# stages_v70.net
KiCad netlist of a schematic drawn in EAGLE
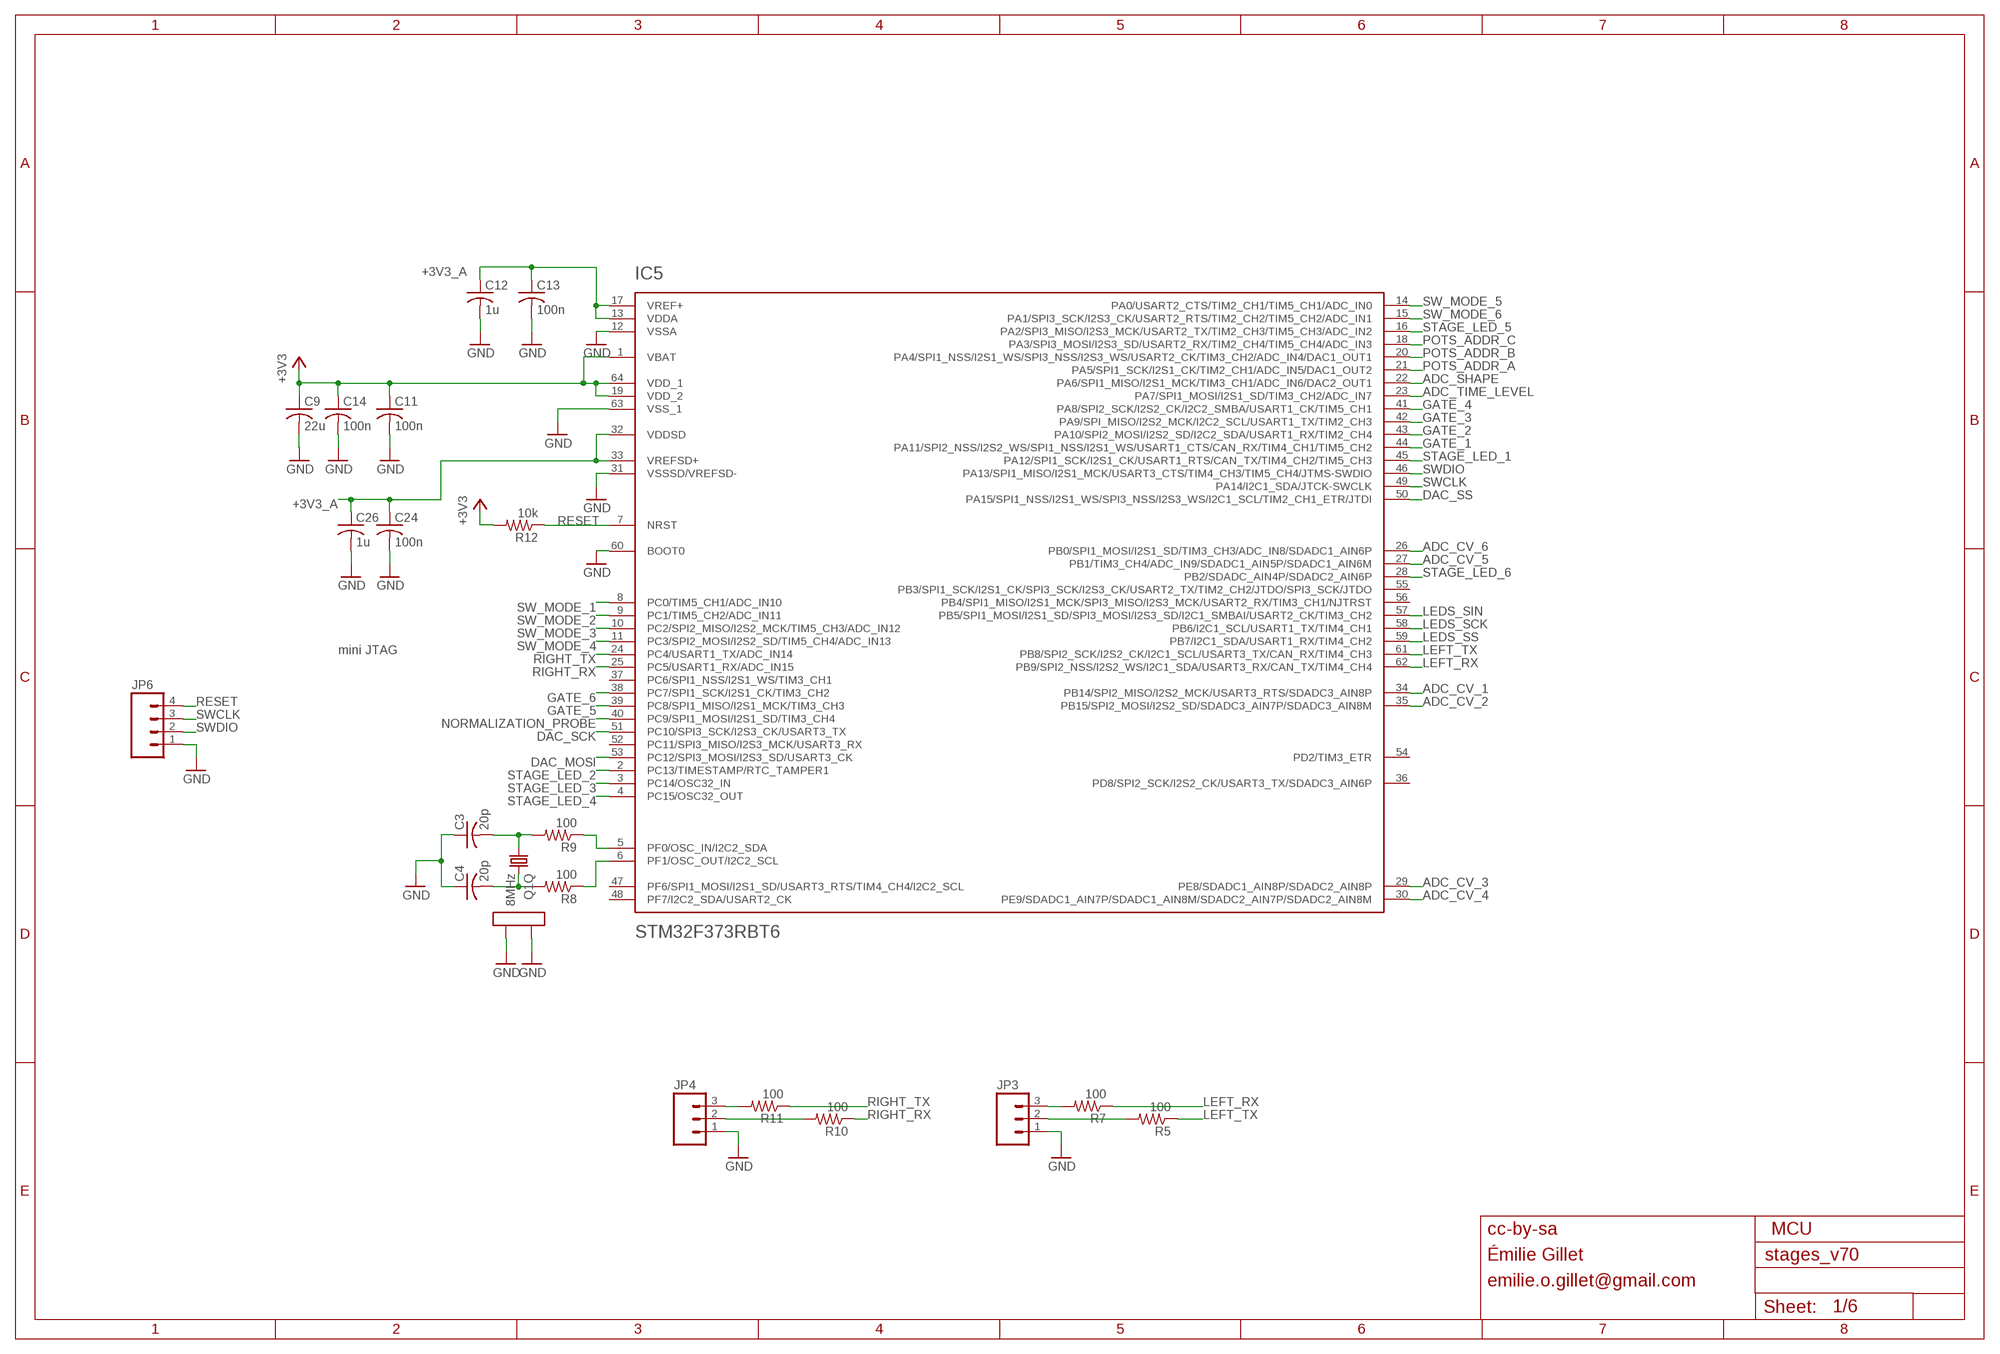
[diagram p0: schematic, sheet 1]
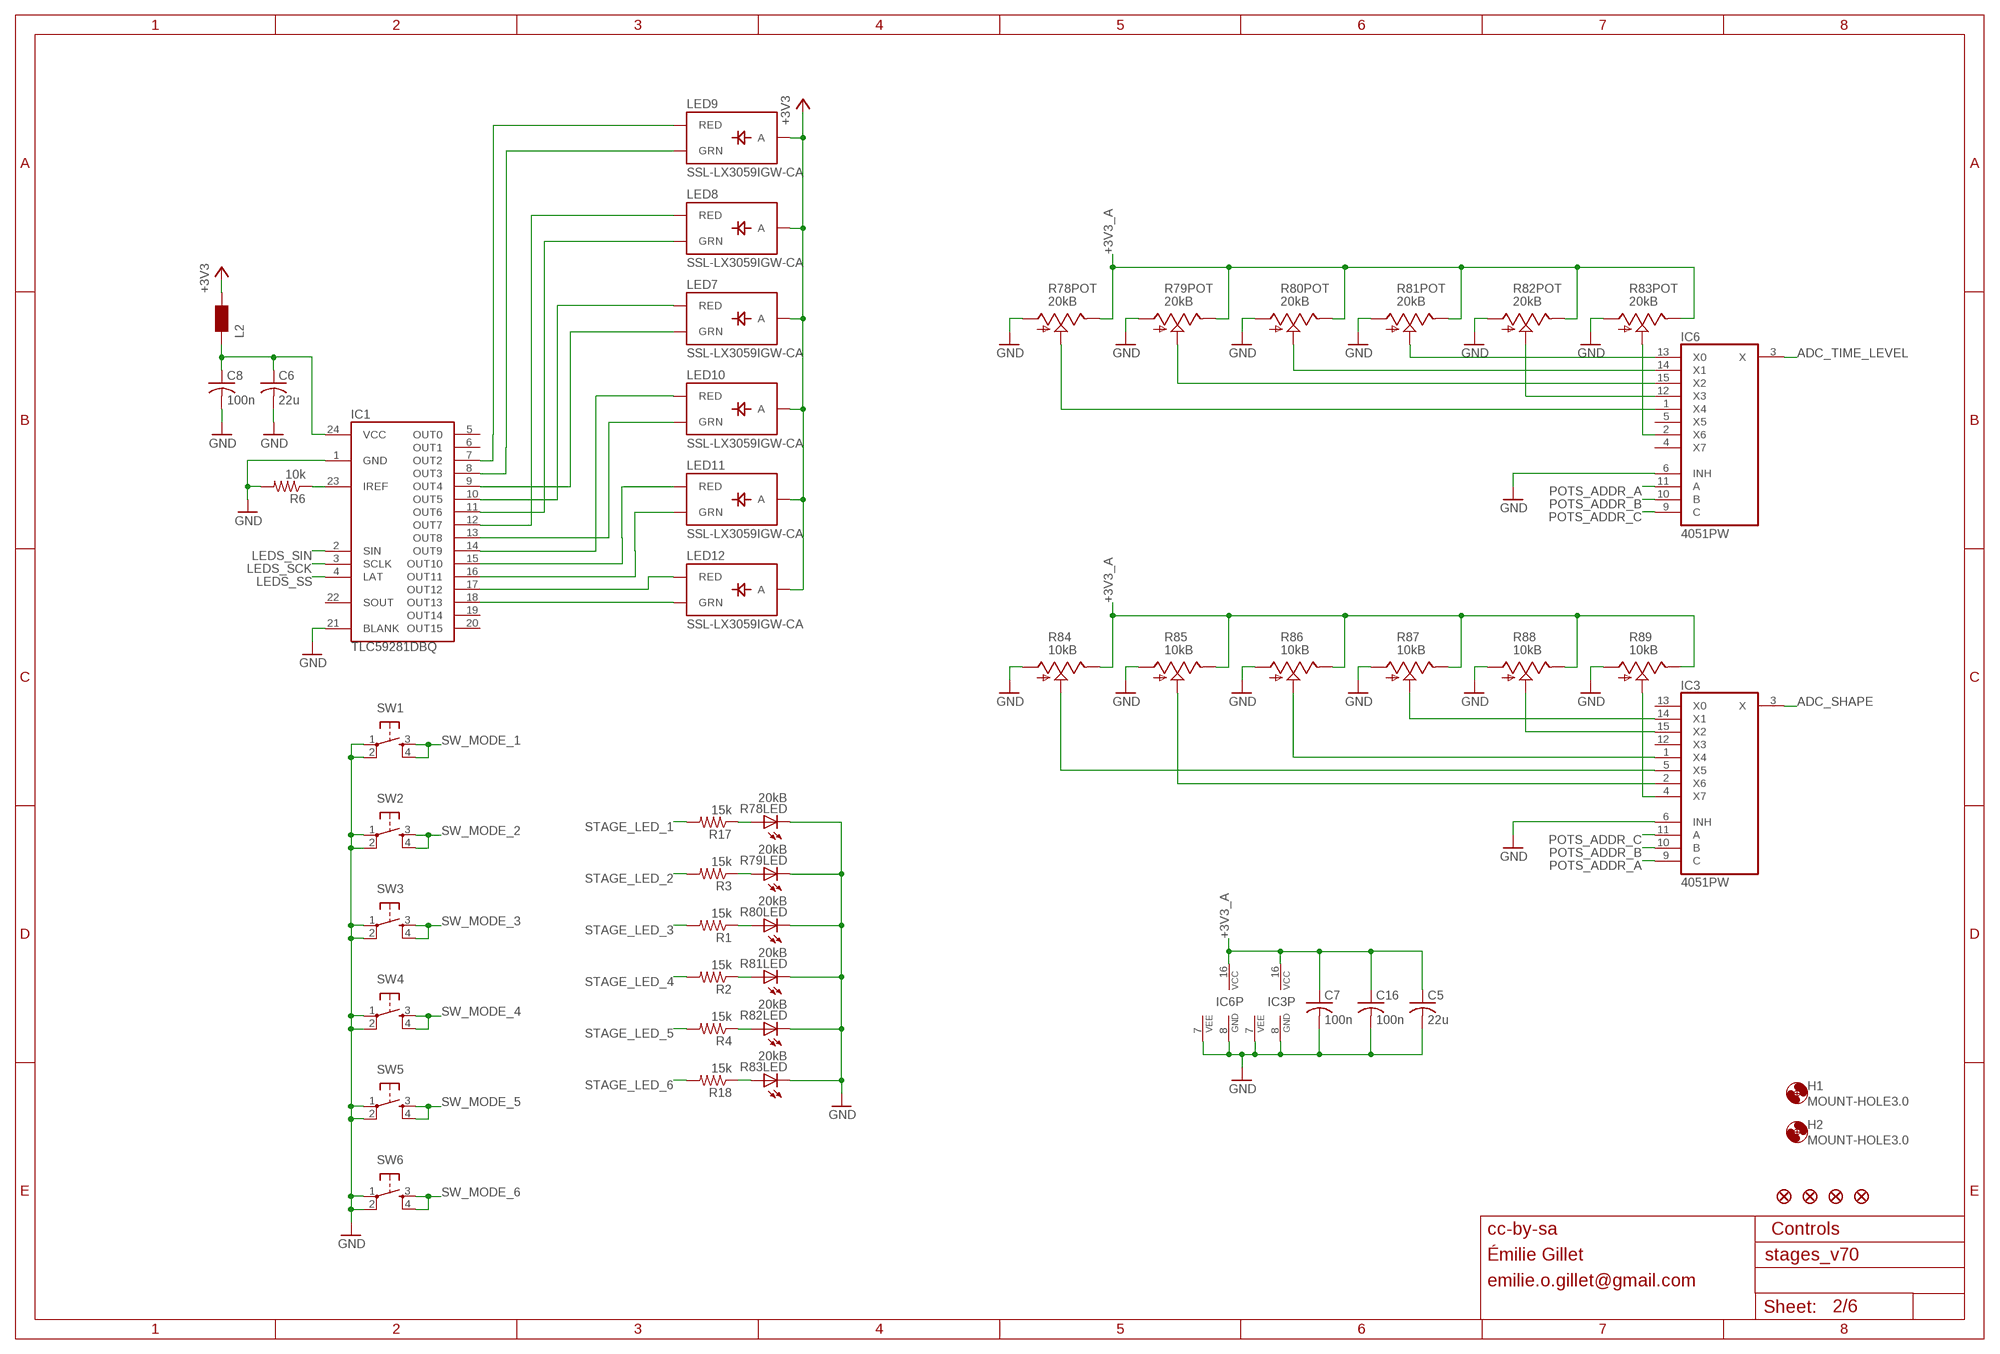
[diagram p1: schematic, sheet 2]
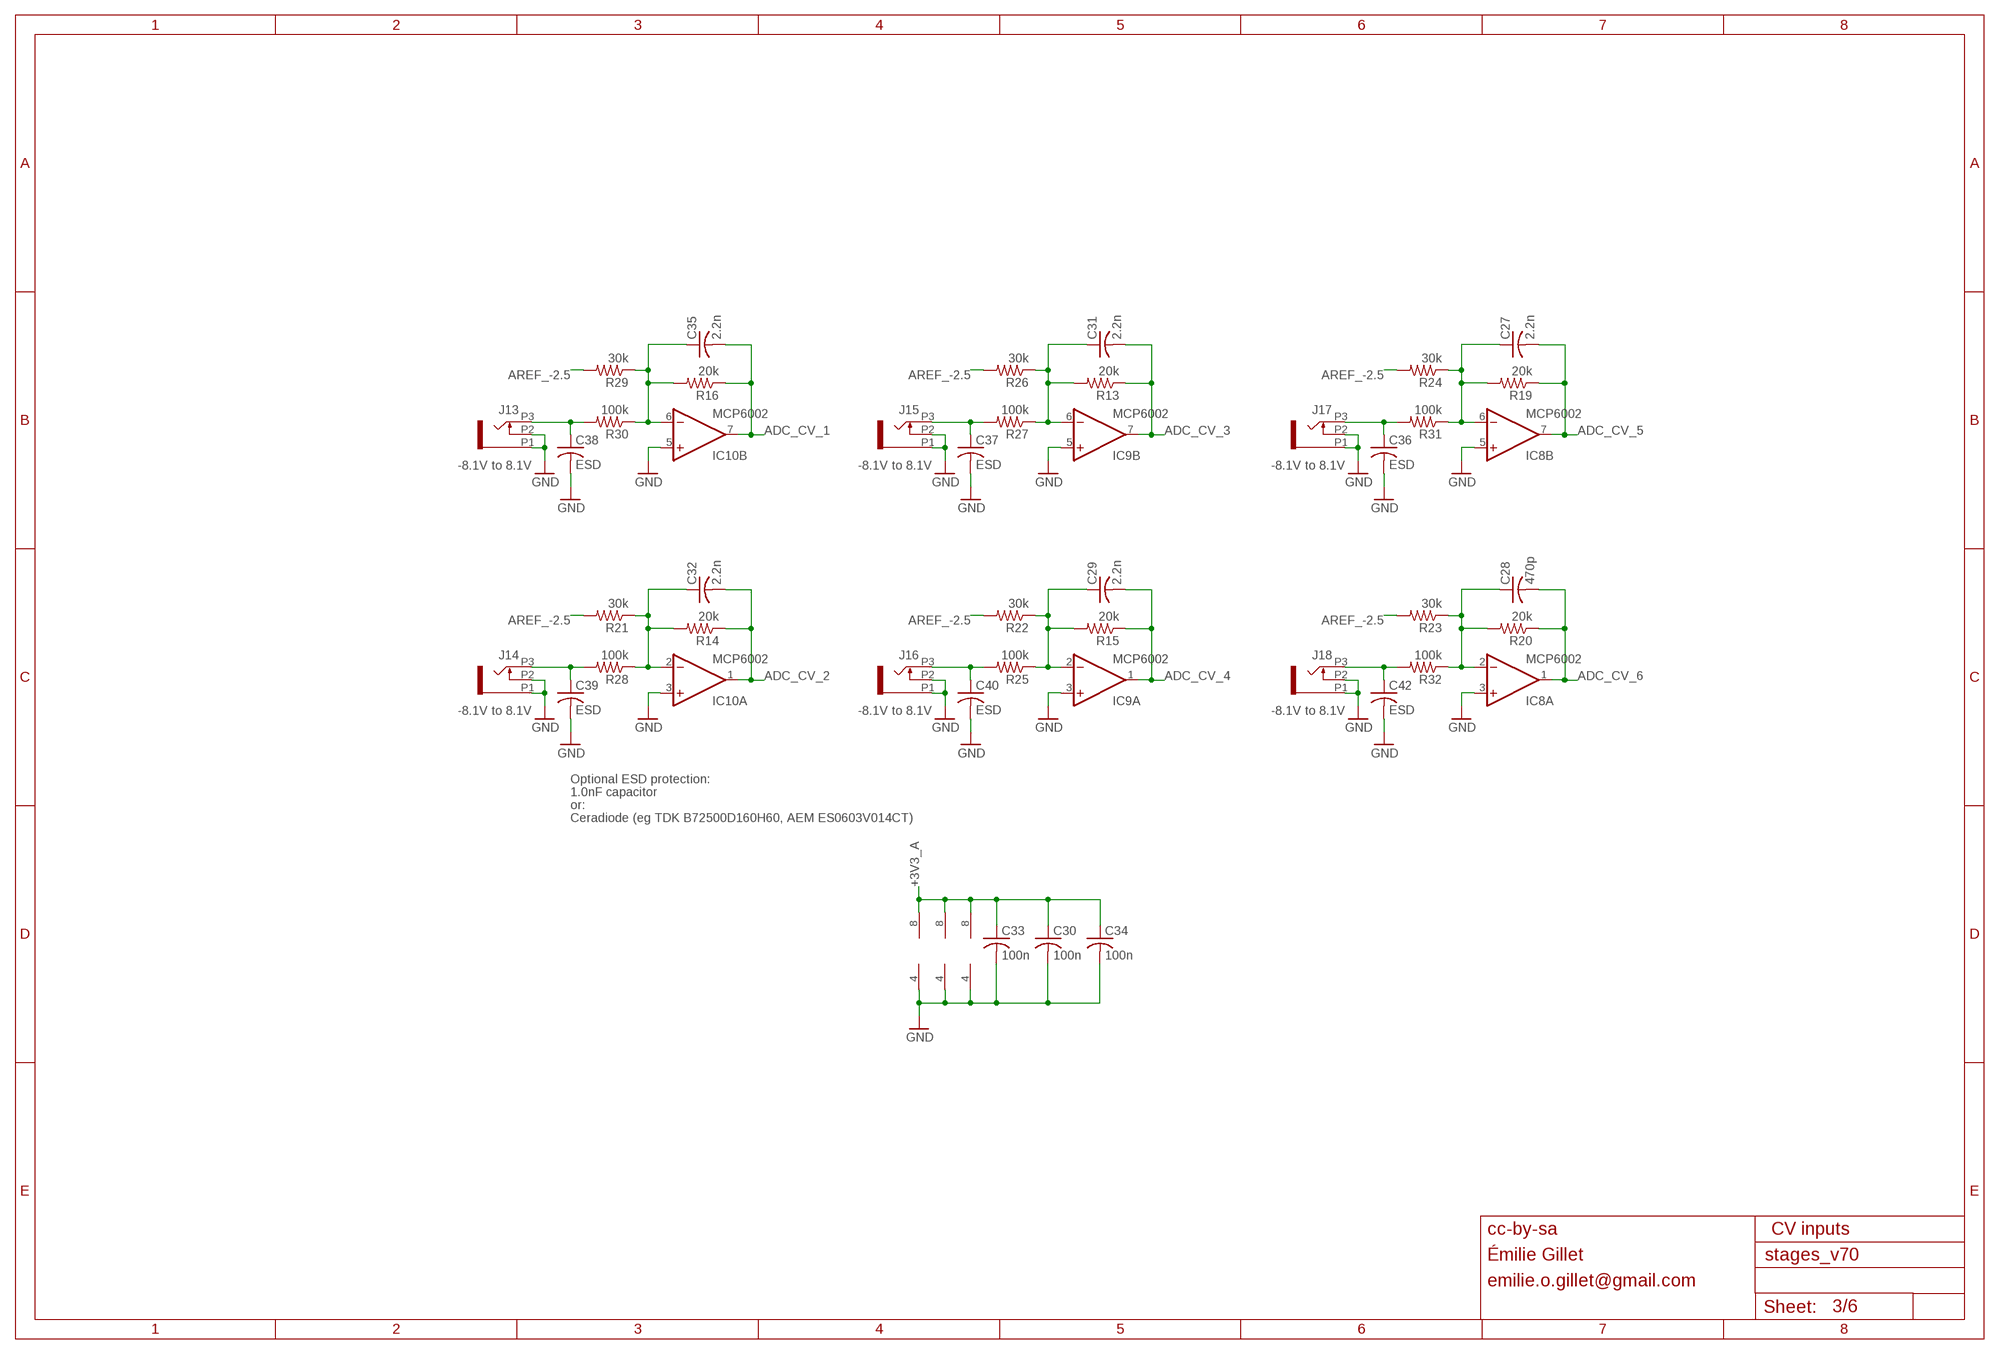
[diagram p2: schematic, sheet 3]
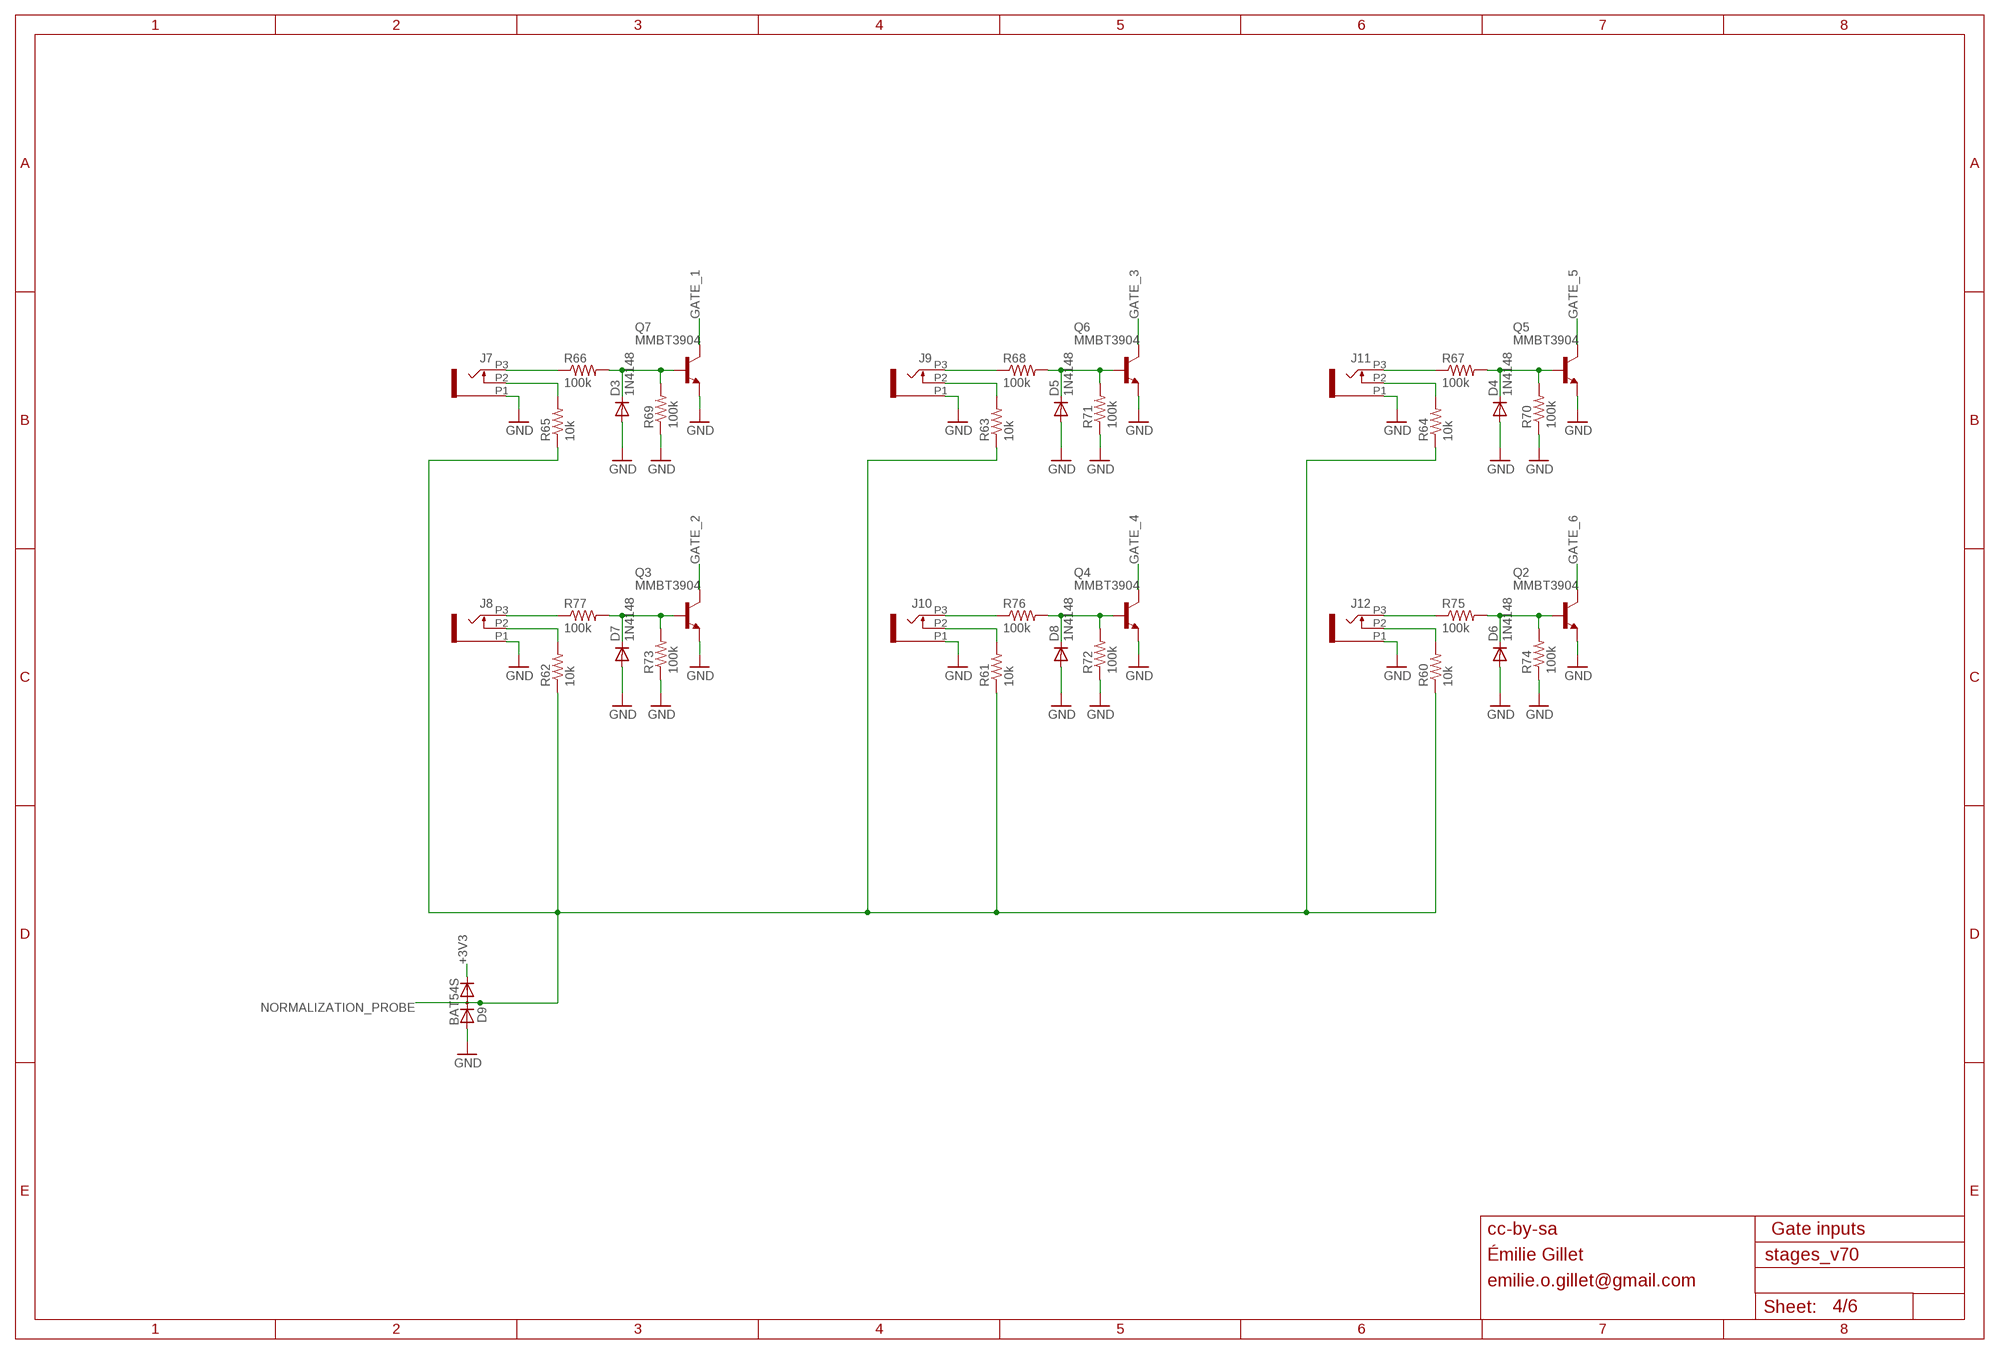
[diagram p3: schematic, sheet 4]
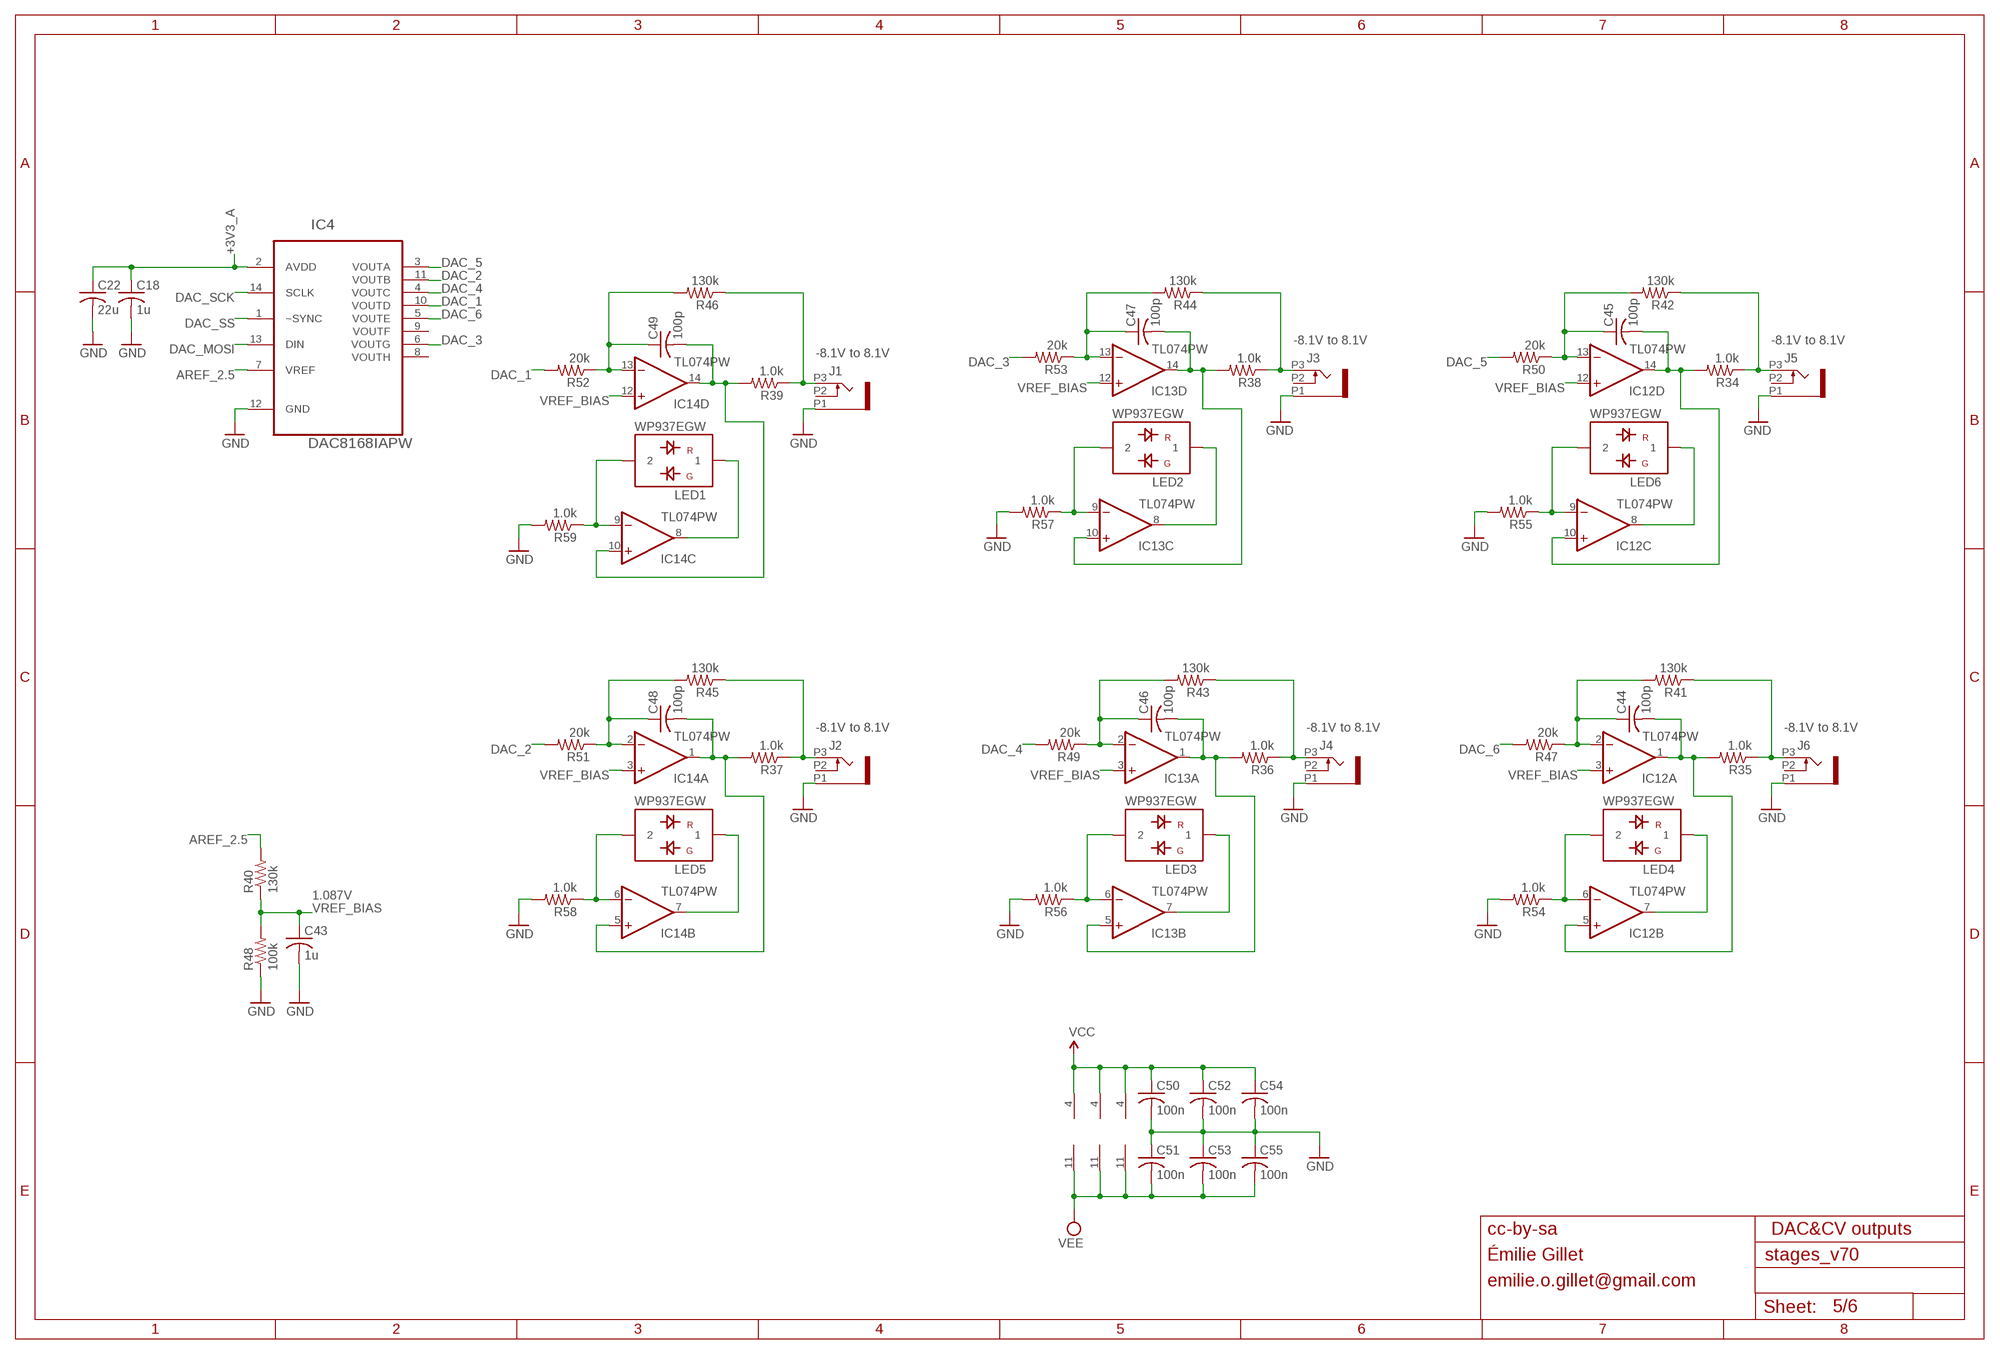
[diagram p4: schematic, sheet 5]
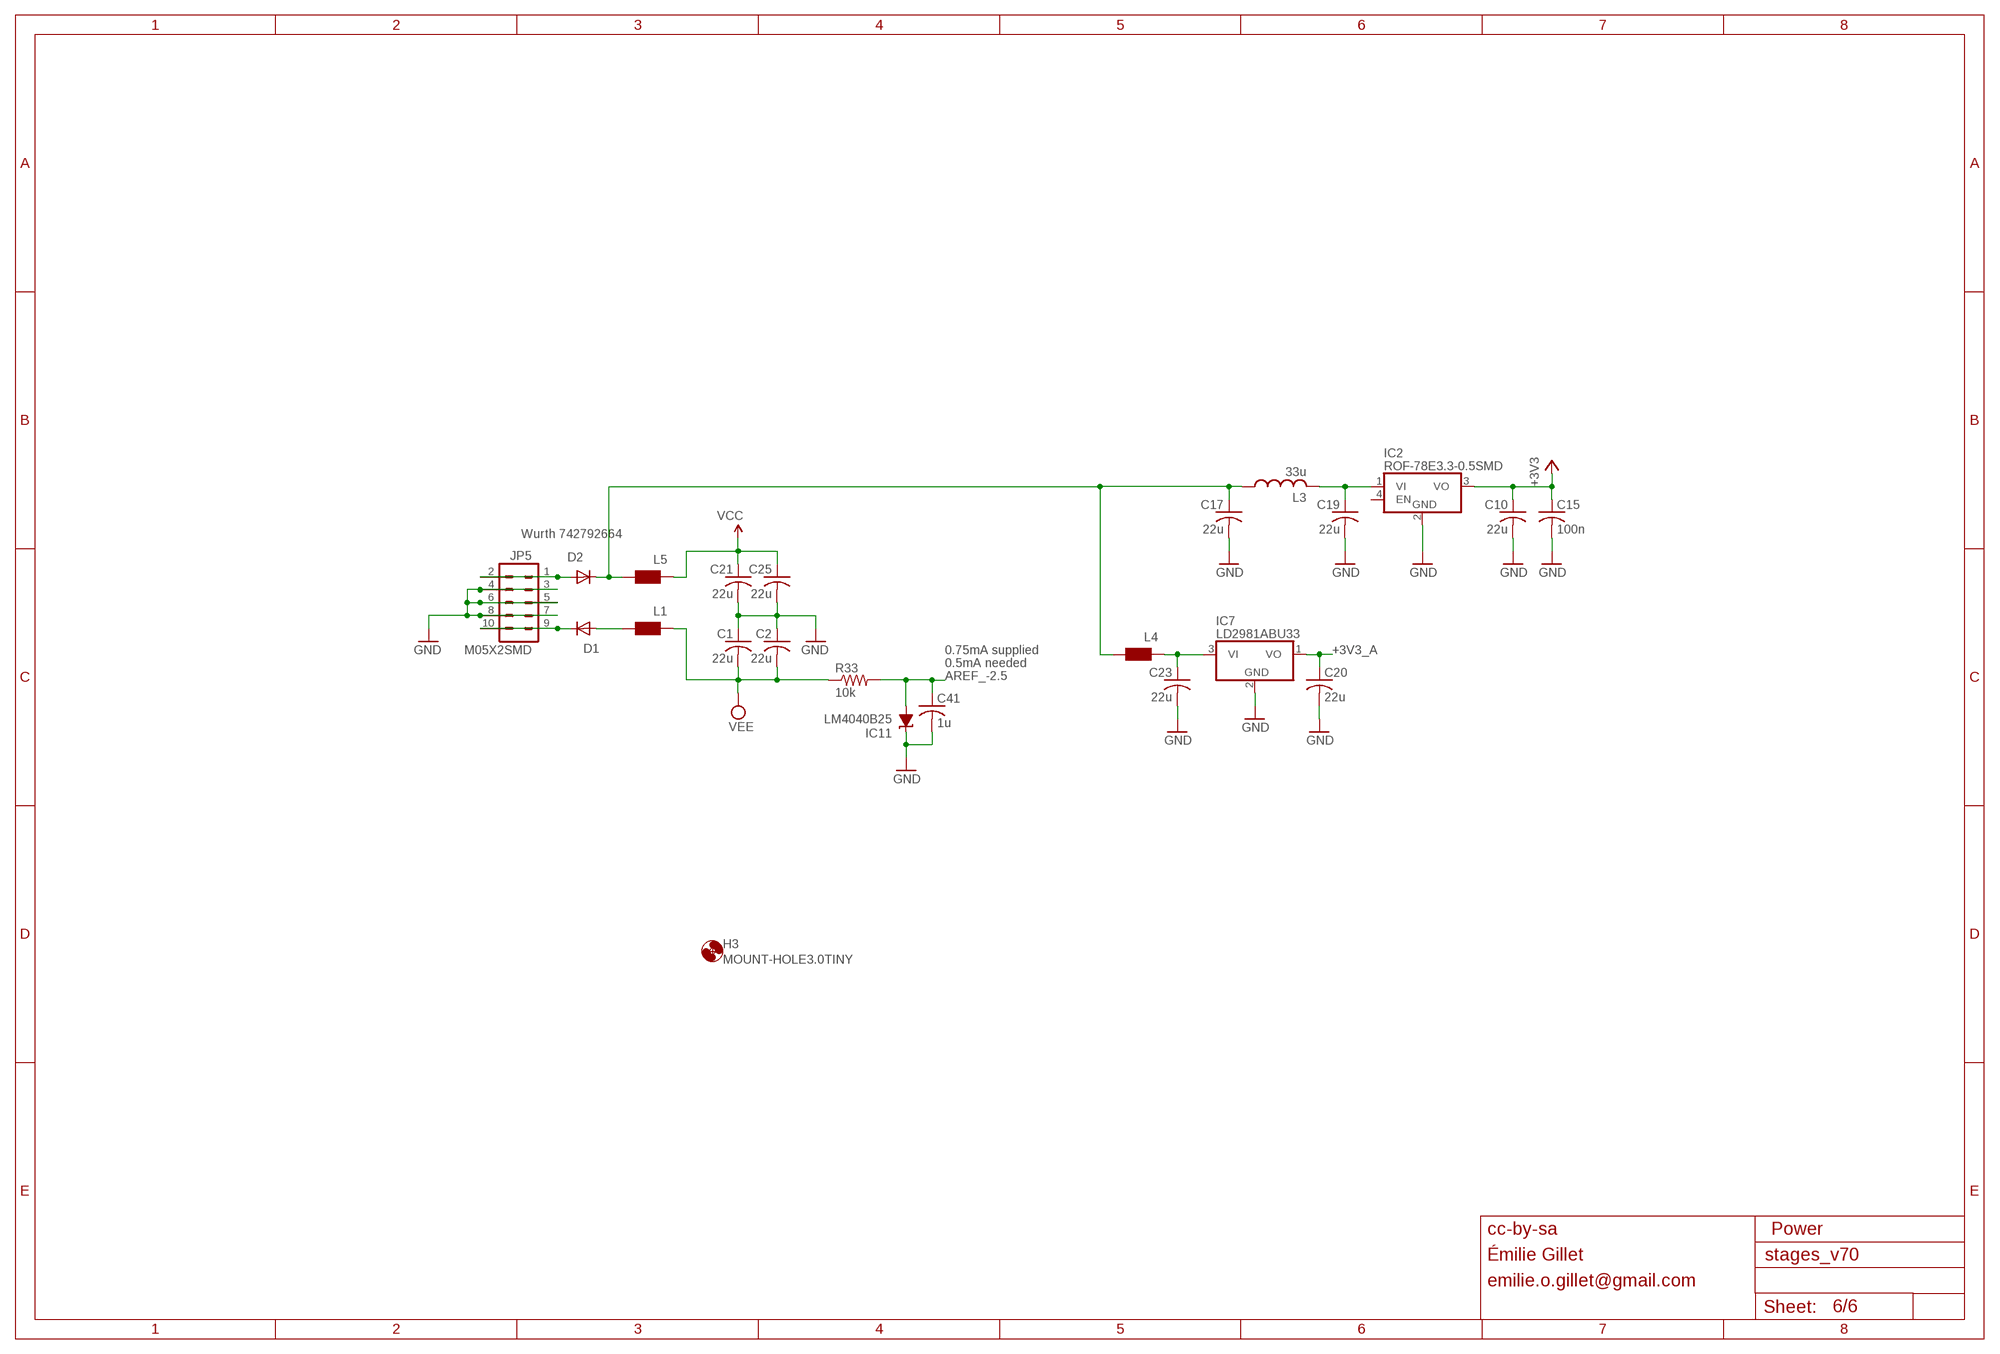
[diagram p5: schematic, sheet 6]

(export (version "E")
  (design (tool "Eeschema 10.0.6"))
  (components
    (comp (ref "C27")
      (value "2.2n")
      (footprint "eagle-import:C0402")
      (libsource (lib "eagle-import") (part "C-USC0402"))
    )
    (comp (ref "C28")
      (value "470p")
      (footprint "eagle-import:C0402")
      (libsource (lib "eagle-import") (part "C-USC0402"))
    )
    (comp (ref "C29")
      (value "2.2n")
      (footprint "eagle-import:C0402")
      (libsource (lib "eagle-import") (part "C-USC0402"))
    )
    (comp (ref "C30")
      (value "100n")
      (footprint "eagle-import:C0402")
      (libsource (lib "eagle-import") (part "C-USC0402"))
    )
    (comp (ref "C31")
      (value "2.2n")
      (footprint "eagle-import:C0402")
      (libsource (lib "eagle-import") (part "C-USC0402"))
    )
    (comp (ref "C32")
      (value "2.2n")
      (footprint "eagle-import:C0402")
      (libsource (lib "eagle-import") (part "C-USC0402"))
    )
    (comp (ref "C33")
      (value "100n")
      (footprint "eagle-import:C0402")
      (libsource (lib "eagle-import") (part "C-USC0402"))
    )
    (comp (ref "C34")
      (value "100n")
      (footprint "eagle-import:C0402")
      (libsource (lib "eagle-import") (part "C-USC0402"))
    )
    (comp (ref "C35")
      (value "2.2n")
      (footprint "eagle-import:C0402")
      (libsource (lib "eagle-import") (part "C-USC0402"))
    )
    (comp (ref "C36")
      (value "ESD")
      (footprint "eagle-import:C0603")
      (libsource (lib "eagle-import") (part "C-USC0603"))
    )
    (comp (ref "C37")
      (value "ESD")
      (footprint "eagle-import:C0603")
      (libsource (lib "eagle-import") (part "C-USC0603"))
    )
    (comp (ref "C38")
      (value "ESD")
      (footprint "eagle-import:C0603")
      (libsource (lib "eagle-import") (part "C-USC0603"))
    )
    (comp (ref "C39")
      (value "ESD")
      (footprint "eagle-import:C0603")
      (libsource (lib "eagle-import") (part "C-USC0603"))
    )
    (comp (ref "C40")
      (value "ESD")
      (footprint "eagle-import:C0603")
      (libsource (lib "eagle-import") (part "C-USC0603"))
    )
    (comp (ref "C42")
      (value "ESD")
      (footprint "eagle-import:C0603")
      (libsource (lib "eagle-import") (part "C-USC0603"))
    )
    (comp (ref "IC8")
      (value "MCP6002")
      (footprint "eagle-import:MSOP-8")
      (libsource (lib "eagle-import") (part "OPA1652DGK"))
    )
    (comp (ref "IC9")
      (value "MCP6002")
      (footprint "eagle-import:MSOP-8")
      (libsource (lib "eagle-import") (part "OPA1652DGK"))
    )
    (comp (ref "IC10")
      (value "MCP6002")
      (footprint "eagle-import:MSOP-8")
      (libsource (lib "eagle-import") (part "OPA1652DGK"))
    )
    (comp (ref "J13")
      (value "PJ301_THONKICONN6")
      (footprint "eagle-import:WQP_PJ_301M6")
      (libsource (lib "eagle-import") (part "PJ301_THONKICONN6"))
    )
    (comp (ref "J14")
      (value "PJ301_THONKICONN6")
      (footprint "eagle-import:WQP_PJ_301M6")
      (libsource (lib "eagle-import") (part "PJ301_THONKICONN6"))
    )
    (comp (ref "J15")
      (value "PJ301_THONKICONN6")
      (footprint "eagle-import:WQP_PJ_301M6")
      (libsource (lib "eagle-import") (part "PJ301_THONKICONN6"))
    )
    (comp (ref "J16")
      (value "PJ301_THONKICONN6")
      (footprint "eagle-import:WQP_PJ_301M6")
      (libsource (lib "eagle-import") (part "PJ301_THONKICONN6"))
    )
    (comp (ref "J17")
      (value "PJ301_THONKICONN6")
      (footprint "eagle-import:WQP_PJ_301M6")
      (libsource (lib "eagle-import") (part "PJ301_THONKICONN6"))
    )
    (comp (ref "J18")
      (value "PJ301_THONKICONN6")
      (footprint "eagle-import:WQP_PJ_301M6")
      (libsource (lib "eagle-import") (part "PJ301_THONKICONN6"))
    )
    (comp (ref "R13")
      (value "20k")
      (footprint "eagle-import:R0402")
      (libsource (lib "eagle-import") (part "R-US_R0402"))
    )
    (comp (ref "R14")
      (value "20k")
      (footprint "eagle-import:R0402")
      (libsource (lib "eagle-import") (part "R-US_R0402"))
    )
    (comp (ref "R15")
      (value "20k")
      (footprint "eagle-import:R0402")
      (libsource (lib "eagle-import") (part "R-US_R0402"))
    )
    (comp (ref "R16")
      (value "20k")
      (footprint "eagle-import:R0402")
      (libsource (lib "eagle-import") (part "R-US_R0402"))
    )
    (comp (ref "R19")
      (value "20k")
      (footprint "eagle-import:R0402")
      (libsource (lib "eagle-import") (part "R-US_R0402"))
    )
    (comp (ref "R20")
      (value "20k")
      (footprint "eagle-import:R0402")
      (libsource (lib "eagle-import") (part "R-US_R0402"))
    )
    (comp (ref "R21")
      (value "30k")
      (footprint "eagle-import:R0402")
      (libsource (lib "eagle-import") (part "R-US_R0402"))
    )
    (comp (ref "R22")
      (value "30k")
      (footprint "eagle-import:R0402")
      (libsource (lib "eagle-import") (part "R-US_R0402"))
    )
    (comp (ref "R23")
      (value "30k")
      (footprint "eagle-import:R0402")
      (libsource (lib "eagle-import") (part "R-US_R0402"))
    )
    (comp (ref "R24")
      (value "30k")
      (footprint "eagle-import:R0402")
      (libsource (lib "eagle-import") (part "R-US_R0402"))
    )
    (comp (ref "R25")
      (value "100k")
      (footprint "eagle-import:R0402")
      (libsource (lib "eagle-import") (part "R-US_R0402"))
    )
    (comp (ref "R26")
      (value "30k")
      (footprint "eagle-import:R0402")
      (libsource (lib "eagle-import") (part "R-US_R0402"))
    )
    (comp (ref "R27")
      (value "100k")
      (footprint "eagle-import:R0402")
      (libsource (lib "eagle-import") (part "R-US_R0402"))
    )
    (comp (ref "R28")
      (value "100k")
      (footprint "eagle-import:R0402")
      (libsource (lib "eagle-import") (part "R-US_R0402"))
    )
    (comp (ref "R29")
      (value "30k")
      (footprint "eagle-import:R0402")
      (libsource (lib "eagle-import") (part "R-US_R0402"))
    )
    (comp (ref "R30")
      (value "100k")
      (footprint "eagle-import:R0402")
      (libsource (lib "eagle-import") (part "R-US_R0402"))
    )
    (comp (ref "R31")
      (value "100k")
      (footprint "eagle-import:R0402")
      (libsource (lib "eagle-import") (part "R-US_R0402"))
    )
    (comp (ref "R32")
      (value "100k")
      (footprint "eagle-import:R0402")
      (libsource (lib "eagle-import") (part "R-US_R0402"))
    )
    (comp (ref "C18")
      (value "1u")
      (footprint "eagle-import:C0402")
      (libsource (lib "eagle-import") (part "C-USC0402"))
    )
    (comp (ref "C22")
      (value "22u")
      (footprint "eagle-import:C1206")
      (libsource (lib "eagle-import") (part "C-USC1206"))
    )
    (comp (ref "C43")
      (value "1u")
      (footprint "eagle-import:C0402")
      (libsource (lib "eagle-import") (part "C-USC0402"))
    )
    (comp (ref "C44")
      (value "100p")
      (footprint "eagle-import:C0402")
      (libsource (lib "eagle-import") (part "C-USC0402"))
    )
    (comp (ref "C45")
      (value "100p")
      (footprint "eagle-import:C0402")
      (libsource (lib "eagle-import") (part "C-USC0402"))
    )
    (comp (ref "C46")
      (value "100p")
      (footprint "eagle-import:C0402")
      (libsource (lib "eagle-import") (part "C-USC0402"))
    )
    (comp (ref "C47")
      (value "100p")
      (footprint "eagle-import:C0402")
      (libsource (lib "eagle-import") (part "C-USC0402"))
    )
    (comp (ref "C48")
      (value "100p")
      (footprint "eagle-import:C0402")
      (libsource (lib "eagle-import") (part "C-USC0402"))
    )
    (comp (ref "C49")
      (value "100p")
      (footprint "eagle-import:C0402")
      (libsource (lib "eagle-import") (part "C-USC0402"))
    )
    (comp (ref "C50")
      (value "100n")
      (footprint "eagle-import:C0402")
      (libsource (lib "eagle-import") (part "C-USC0402"))
    )
    (comp (ref "C51")
      (value "100n")
      (footprint "eagle-import:C0402")
      (libsource (lib "eagle-import") (part "C-USC0402"))
    )
    (comp (ref "C52")
      (value "100n")
      (footprint "eagle-import:C0402")
      (libsource (lib "eagle-import") (part "C-USC0402"))
    )
    (comp (ref "C53")
      (value "100n")
      (footprint "eagle-import:C0402")
      (libsource (lib "eagle-import") (part "C-USC0402"))
    )
    (comp (ref "C54")
      (value "100n")
      (footprint "eagle-import:C0402")
      (libsource (lib "eagle-import") (part "C-USC0402"))
    )
    (comp (ref "C55")
      (value "100n")
      (footprint "eagle-import:C0402")
      (libsource (lib "eagle-import") (part "C-USC0402"))
    )
    (comp (ref "IC4")
      (value "DAC8168IAPW")
      (footprint "eagle-import:RPDSOG14")
      (libsource (lib "eagle-import") (part "DAC8168PW"))
    )
    (comp (ref "IC12")
      (value "TL074PW")
      (footprint "eagle-import:TSSOP14_065")
      (libsource (lib "eagle-import") (part "TL074PW"))
    )
    (comp (ref "IC13")
      (value "TL074PW")
      (footprint "eagle-import:TSSOP14_065")
      (libsource (lib "eagle-import") (part "TL074PW"))
    )
    (comp (ref "IC14")
      (value "TL074PW")
      (footprint "eagle-import:TSSOP14_065")
      (libsource (lib "eagle-import") (part "TL074PW"))
    )
    (comp (ref "J1")
      (value "PJ301_THONKICONN6")
      (footprint "eagle-import:WQP_PJ_301M6")
      (libsource (lib "eagle-import") (part "PJ301_THONKICONN6"))
    )
    (comp (ref "J2")
      (value "PJ301_THONKICONN6")
      (footprint "eagle-import:WQP_PJ_301M6")
      (libsource (lib "eagle-import") (part "PJ301_THONKICONN6"))
    )
    (comp (ref "J3")
      (value "PJ301_THONKICONN6")
      (footprint "eagle-import:WQP_PJ_301M6")
      (libsource (lib "eagle-import") (part "PJ301_THONKICONN6"))
    )
    (comp (ref "J4")
      (value "PJ301_THONKICONN6")
      (footprint "eagle-import:WQP_PJ_301M6")
      (libsource (lib "eagle-import") (part "PJ301_THONKICONN6"))
    )
    (comp (ref "J5")
      (value "PJ301_THONKICONN6")
      (footprint "eagle-import:WQP_PJ_301M6")
      (libsource (lib "eagle-import") (part "PJ301_THONKICONN6"))
    )
    (comp (ref "J6")
      (value "PJ301_THONKICONN6")
      (footprint "eagle-import:WQP_PJ_301M6")
      (libsource (lib "eagle-import") (part "PJ301_THONKICONN6"))
    )
    (comp (ref "LED1")
      (value "WP937EGW")
      (footprint "eagle-import:LED3MM")
      (libsource (lib "eagle-import") (part "LED-BICOLOR-SHARED-THROUGHHOLE"))
    )
    (comp (ref "LED2")
      (value "WP937EGW")
      (footprint "eagle-import:LED3MM")
      (libsource (lib "eagle-import") (part "LED-BICOLOR-SHARED-THROUGHHOLE"))
    )
    (comp (ref "LED3")
      (value "WP937EGW")
      (footprint "eagle-import:LED3MM")
      (libsource (lib "eagle-import") (part "LED-BICOLOR-SHARED-THROUGHHOLE"))
    )
    (comp (ref "LED4")
      (value "WP937EGW")
      (footprint "eagle-import:LED3MM")
      (libsource (lib "eagle-import") (part "LED-BICOLOR-SHARED-THROUGHHOLE"))
    )
    (comp (ref "LED5")
      (value "WP937EGW")
      (footprint "eagle-import:LED3MM")
      (libsource (lib "eagle-import") (part "LED-BICOLOR-SHARED-THROUGHHOLE"))
    )
    (comp (ref "LED6")
      (value "WP937EGW")
      (footprint "eagle-import:LED3MM")
      (libsource (lib "eagle-import") (part "LED-BICOLOR-SHARED-THROUGHHOLE"))
    )
    (comp (ref "R34")
      (value "1.0k")
      (footprint "eagle-import:R0603")
      (libsource (lib "eagle-import") (part "R-US_R0603"))
    )
    (comp (ref "R35")
      (value "1.0k")
      (footprint "eagle-import:R0603")
      (libsource (lib "eagle-import") (part "R-US_R0603"))
    )
    (comp (ref "R36")
      (value "1.0k")
      (footprint "eagle-import:R0603")
      (libsource (lib "eagle-import") (part "R-US_R0603"))
    )
    (comp (ref "R37")
      (value "1.0k")
      (footprint "eagle-import:R0603")
      (libsource (lib "eagle-import") (part "R-US_R0603"))
    )
    (comp (ref "R38")
      (value "1.0k")
      (footprint "eagle-import:R0603")
      (libsource (lib "eagle-import") (part "R-US_R0603"))
    )
    (comp (ref "R39")
      (value "1.0k")
      (footprint "eagle-import:R0603")
      (libsource (lib "eagle-import") (part "R-US_R0603"))
    )
    (comp (ref "R40")
      (value "130k")
      (footprint "eagle-import:R0402")
      (libsource (lib "eagle-import") (part "R-US_R0402"))
    )
    (comp (ref "R41")
      (value "130k")
      (footprint "eagle-import:R0402")
      (libsource (lib "eagle-import") (part "R-US_R0402"))
    )
    (comp (ref "R42")
      (value "130k")
      (footprint "eagle-import:R0402")
      (libsource (lib "eagle-import") (part "R-US_R0402"))
    )
    (comp (ref "R43")
      (value "130k")
      (footprint "eagle-import:R0402")
      (libsource (lib "eagle-import") (part "R-US_R0402"))
    )
    (comp (ref "R44")
      (value "130k")
      (footprint "eagle-import:R0402")
      (libsource (lib "eagle-import") (part "R-US_R0402"))
    )
    (comp (ref "R45")
      (value "130k")
      (footprint "eagle-import:R0402")
      (libsource (lib "eagle-import") (part "R-US_R0402"))
    )
    (comp (ref "R46")
      (value "130k")
      (footprint "eagle-import:R0402")
      (libsource (lib "eagle-import") (part "R-US_R0402"))
    )
    (comp (ref "R47")
      (value "20k")
      (footprint "eagle-import:R0402")
      (libsource (lib "eagle-import") (part "R-US_R0402"))
    )
    (comp (ref "R48")
      (value "100k")
      (footprint "eagle-import:R0402")
      (libsource (lib "eagle-import") (part "R-US_R0402"))
    )
    (comp (ref "R49")
      (value "20k")
      (footprint "eagle-import:R0402")
      (libsource (lib "eagle-import") (part "R-US_R0402"))
    )
    (comp (ref "R50")
      (value "20k")
      (footprint "eagle-import:R0402")
      (libsource (lib "eagle-import") (part "R-US_R0402"))
    )
    (comp (ref "R51")
      (value "20k")
      (footprint "eagle-import:R0402")
      (libsource (lib "eagle-import") (part "R-US_R0402"))
    )
    (comp (ref "R52")
      (value "20k")
      (footprint "eagle-import:R0402")
      (libsource (lib "eagle-import") (part "R-US_R0402"))
    )
    (comp (ref "R53")
      (value "20k")
      (footprint "eagle-import:R0402")
      (libsource (lib "eagle-import") (part "R-US_R0402"))
    )
    (comp (ref "R54")
      (value "1.0k")
      (footprint "eagle-import:R0402")
      (libsource (lib "eagle-import") (part "R-US_R0402"))
    )
    (comp (ref "R55")
      (value "1.0k")
      (footprint "eagle-import:R0402")
      (libsource (lib "eagle-import") (part "R-US_R0402"))
    )
    (comp (ref "R56")
      (value "1.0k")
      (footprint "eagle-import:R0402")
      (libsource (lib "eagle-import") (part "R-US_R0402"))
    )
    (comp (ref "R57")
      (value "1.0k")
      (footprint "eagle-import:R0402")
      (libsource (lib "eagle-import") (part "R-US_R0402"))
    )
    (comp (ref "R58")
      (value "1.0k")
      (footprint "eagle-import:R0402")
      (libsource (lib "eagle-import") (part "R-US_R0402"))
    )
    (comp (ref "R59")
      (value "1.0k")
      (footprint "eagle-import:R0402")
      (libsource (lib "eagle-import") (part "R-US_R0402"))
    )
    (comp (ref "C3")
      (value "20p")
      (footprint "eagle-import:C0402")
      (libsource (lib "eagle-import") (part "C-USC0402"))
    )
    (comp (ref "C4")
      (value "20p")
      (footprint "eagle-import:C0402")
      (libsource (lib "eagle-import") (part "C-USC0402"))
    )
    (comp (ref "C9")
      (value "22u")
      (footprint "eagle-import:C1206")
      (libsource (lib "eagle-import") (part "C-USC1206"))
    )
    (comp (ref "C11")
      (value "100n")
      (footprint "eagle-import:C0402")
      (libsource (lib "eagle-import") (part "C-USC0402"))
    )
    (comp (ref "C12")
      (value "1u")
      (footprint "eagle-import:C0402")
      (libsource (lib "eagle-import") (part "C-USC0402"))
    )
    (comp (ref "C13")
      (value "100n")
      (footprint "eagle-import:C0402")
      (libsource (lib "eagle-import") (part "C-USC0402"))
    )
    (comp (ref "C14")
      (value "100n")
      (footprint "eagle-import:C0402")
      (libsource (lib "eagle-import") (part "C-USC0402"))
    )
    (comp (ref "C24")
      (value "100n")
      (footprint "eagle-import:C0402")
      (libsource (lib "eagle-import") (part "C-USC0402"))
    )
    (comp (ref "C26")
      (value "1u")
      (footprint "eagle-import:C0402")
      (libsource (lib "eagle-import") (part "C-USC0402"))
    )
    (comp (ref "IC5")
      (value "STM32F373RBT6")
      (footprint "eagle-import:TQFP-10X10-64")
      (libsource (lib "eagle-import") (part "STM32F373R"))
    )
    (comp (ref "JP3")
      (value "M03PTH")
      (footprint "eagle-import:1X03")
      (libsource (lib "eagle-import") (part "M03PTH"))
    )
    (comp (ref "JP4")
      (value "M03PTH")
      (footprint "eagle-import:1X03")
      (libsource (lib "eagle-import") (part "M03PTH"))
    )
    (comp (ref "JP6")
      (value "M04PTH")
      (footprint "eagle-import:1X04")
      (libsource (lib "eagle-import") (part "M04PTH"))
    )
    (comp (ref "Q1")
      (value "8MHz")
      (footprint "eagle-import:CTS406")
      (libsource (lib "eagle-import") (part "CRYSTAL"))
    )
    (comp (ref "R5")
      (value "100")
      (footprint "eagle-import:R0402")
      (libsource (lib "eagle-import") (part "R-US_R0402"))
    )
    (comp (ref "R7")
      (value "100")
      (footprint "eagle-import:R0402")
      (libsource (lib "eagle-import") (part "R-US_R0402"))
    )
    (comp (ref "R8")
      (value "100")
      (footprint "eagle-import:R0402")
      (libsource (lib "eagle-import") (part "R-US_R0402"))
    )
    (comp (ref "R9")
      (value "100")
      (footprint "eagle-import:R0402")
      (libsource (lib "eagle-import") (part "R-US_R0402"))
    )
    (comp (ref "R10")
      (value "100")
      (footprint "eagle-import:R0402")
      (libsource (lib "eagle-import") (part "R-US_R0402"))
    )
    (comp (ref "R11")
      (value "100")
      (footprint "eagle-import:R0402")
      (libsource (lib "eagle-import") (part "R-US_R0402"))
    )
    (comp (ref "R12")
      (value "10k")
      (footprint "eagle-import:R0402")
      (libsource (lib "eagle-import") (part "R-US_R0402"))
    )
    (comp (ref "C5")
      (value "22u")
      (footprint "eagle-import:C1206")
      (libsource (lib "eagle-import") (part "C-USC1206"))
    )
    (comp (ref "C6")
      (value "22u")
      (footprint "eagle-import:C1206")
      (libsource (lib "eagle-import") (part "C-USC1206"))
    )
    (comp (ref "C7")
      (value "100n")
      (footprint "eagle-import:C0402")
      (libsource (lib "eagle-import") (part "C-USC0402"))
    )
    (comp (ref "C8")
      (value "100n")
      (footprint "eagle-import:C0402")
      (libsource (lib "eagle-import") (part "C-USC0402"))
    )
    (comp (ref "C16")
      (value "100n")
      (footprint "eagle-import:C0402")
      (libsource (lib "eagle-import") (part "C-USC0402"))
    )
    (comp (ref "H1")
      (value "MOUNT-HOLE3.0")
      (footprint "eagle-import:3,0")
      (libsource (lib "eagle-import") (part "MOUNT-HOLE3.0"))
    )
    (comp (ref "H2")
      (value "MOUNT-HOLE3.0")
      (footprint "eagle-import:3,0")
      (libsource (lib "eagle-import") (part "MOUNT-HOLE3.0"))
    )
    (comp (ref "IC1")
      (value "TLC59281DBQ")
      (footprint "eagle-import:TSSOP24_0635")
      (libsource (lib "eagle-import") (part "TLC59281DBQ"))
    )
    (comp (ref "IC3")
      (value "4051PW")
      (footprint "eagle-import:TSSOP16_065")
      (libsource (lib "eagle-import") (part "4051PW"))
    )
    (comp (ref "IC6")
      (value "4051PW")
      (footprint "eagle-import:TSSOP16_065")
      (libsource (lib "eagle-import") (part "4051PW"))
    )
    (comp (ref "JP1")
      (value "FIDUCIAL1X2")
      (footprint "eagle-import:FIDUCIAL-1X2")
      (libsource (lib "eagle-import") (part "FIDUCIAL1X2"))
    )
    (comp (ref "JP2")
      (value "FIDUCIAL1X2")
      (footprint "eagle-import:FIDUCIAL-1X2")
      (libsource (lib "eagle-import") (part "FIDUCIAL1X2"))
    )
    (comp (ref "JP7")
      (value "FIDUCIAL1X2")
      (footprint "eagle-import:FIDUCIAL-1X2")
      (libsource (lib "eagle-import") (part "FIDUCIAL1X2"))
    )
    (comp (ref "JP8")
      (value "FIDUCIAL1X2")
      (footprint "eagle-import:FIDUCIAL-1X2")
      (libsource (lib "eagle-import") (part "FIDUCIAL1X2"))
    )
    (comp (ref "L2")
      (value "WE-CBF_0603")
      (footprint "eagle-import:0603")
      (libsource (lib "eagle-import") (part "WE-CBF_0603"))
    )
    (comp (ref "LED7")
      (value "SSL-LX3059IGW-CA")
      (footprint "eagle-import:LED-BICOLOR-THROUGHHOLE-LUMEX")
      (libsource (lib "eagle-import") (part "LED-BICOLOR-THROUGHHOLE-CA"))
    )
    (comp (ref "LED8")
      (value "SSL-LX3059IGW-CA")
      (footprint "eagle-import:LED-BICOLOR-THROUGHHOLE-LUMEX")
      (libsource (lib "eagle-import") (part "LED-BICOLOR-THROUGHHOLE-CA"))
    )
    (comp (ref "LED9")
      (value "SSL-LX3059IGW-CA")
      (footprint "eagle-import:LED-BICOLOR-THROUGHHOLE-LUMEX")
      (libsource (lib "eagle-import") (part "LED-BICOLOR-THROUGHHOLE-CA"))
    )
    (comp (ref "LED10")
      (value "SSL-LX3059IGW-CA")
      (footprint "eagle-import:LED-BICOLOR-THROUGHHOLE-LUMEX")
      (libsource (lib "eagle-import") (part "LED-BICOLOR-THROUGHHOLE-CA"))
    )
    (comp (ref "LED11")
      (value "SSL-LX3059IGW-CA")
      (footprint "eagle-import:LED-BICOLOR-THROUGHHOLE-LUMEX")
      (libsource (lib "eagle-import") (part "LED-BICOLOR-THROUGHHOLE-CA"))
    )
    (comp (ref "LED12")
      (value "SSL-LX3059IGW-CA")
      (footprint "eagle-import:LED-BICOLOR-THROUGHHOLE-LUMEX")
      (libsource (lib "eagle-import") (part "LED-BICOLOR-THROUGHHOLE-CA"))
    )
    (comp (ref "R1")
      (value "15k")
      (footprint "eagle-import:R0402")
      (libsource (lib "eagle-import") (part "R-US_R0402"))
    )
    (comp (ref "R2")
      (value "15k")
      (footprint "eagle-import:R0402")
      (libsource (lib "eagle-import") (part "R-US_R0402"))
    )
    (comp (ref "R3")
      (value "15k")
      (footprint "eagle-import:R0402")
      (libsource (lib "eagle-import") (part "R-US_R0402"))
    )
    (comp (ref "R4")
      (value "15k")
      (footprint "eagle-import:R0402")
      (libsource (lib "eagle-import") (part "R-US_R0402"))
    )
    (comp (ref "R6")
      (value "10k")
      (footprint "eagle-import:R0402")
      (libsource (lib "eagle-import") (part "R-US_R0402"))
    )
    (comp (ref "R17")
      (value "15k")
      (footprint "eagle-import:R0402")
      (libsource (lib "eagle-import") (part "R-US_R0402"))
    )
    (comp (ref "R18")
      (value "15k")
      (footprint "eagle-import:R0402")
      (libsource (lib "eagle-import") (part "R-US_R0402"))
    )
    (comp (ref "R78")
      (value "20kB")
      (footprint "eagle-import:BOURNS_SLIDER")
      (libsource (lib "eagle-import") (part "BOURNS_SLIDER"))
    )
    (comp (ref "R79")
      (value "20kB")
      (footprint "eagle-import:BOURNS_SLIDER")
      (libsource (lib "eagle-import") (part "BOURNS_SLIDER"))
    )
    (comp (ref "R80")
      (value "20kB")
      (footprint "eagle-import:BOURNS_SLIDER")
      (libsource (lib "eagle-import") (part "BOURNS_SLIDER"))
    )
    (comp (ref "R81")
      (value "20kB")
      (footprint "eagle-import:BOURNS_SLIDER")
      (libsource (lib "eagle-import") (part "BOURNS_SLIDER"))
    )
    (comp (ref "R82")
      (value "20kB")
      (footprint "eagle-import:BOURNS_SLIDER")
      (libsource (lib "eagle-import") (part "BOURNS_SLIDER"))
    )
    (comp (ref "R83")
      (value "20kB")
      (footprint "eagle-import:BOURNS_SLIDER")
      (libsource (lib "eagle-import") (part "BOURNS_SLIDER"))
    )
    (comp (ref "R84")
      (value "10kB")
      (footprint "eagle-import:ALPS_POT_NARROW")
      (libsource (lib "eagle-import") (part "POT_USVERTICAL_NARROW"))
    )
    (comp (ref "R85")
      (value "10kB")
      (footprint "eagle-import:ALPS_POT_NARROW")
      (libsource (lib "eagle-import") (part "POT_USVERTICAL_NARROW"))
    )
    (comp (ref "R86")
      (value "10kB")
      (footprint "eagle-import:ALPS_POT_NARROW")
      (libsource (lib "eagle-import") (part "POT_USVERTICAL_NARROW"))
    )
    (comp (ref "R87")
      (value "10kB")
      (footprint "eagle-import:ALPS_POT_NARROW")
      (libsource (lib "eagle-import") (part "POT_USVERTICAL_NARROW"))
    )
    (comp (ref "R88")
      (value "10kB")
      (footprint "eagle-import:ALPS_POT_NARROW")
      (libsource (lib "eagle-import") (part "POT_USVERTICAL_NARROW"))
    )
    (comp (ref "R89")
      (value "10kB")
      (footprint "eagle-import:ALPS_POT_NARROW")
      (libsource (lib "eagle-import") (part "POT_USVERTICAL_NARROW"))
    )
    (comp (ref "SW1")
      (value "TAC_SWITCHPTH")
      (footprint "eagle-import:TACTILE-PTH")
      (libsource (lib "eagle-import") (part "TAC_SWITCHPTH"))
    )
    (comp (ref "SW2")
      (value "TAC_SWITCHPTH")
      (footprint "eagle-import:TACTILE-PTH")
      (libsource (lib "eagle-import") (part "TAC_SWITCHPTH"))
    )
    (comp (ref "SW3")
      (value "TAC_SWITCHPTH")
      (footprint "eagle-import:TACTILE-PTH")
      (libsource (lib "eagle-import") (part "TAC_SWITCHPTH"))
    )
    (comp (ref "SW4")
      (value "TAC_SWITCHPTH")
      (footprint "eagle-import:TACTILE-PTH")
      (libsource (lib "eagle-import") (part "TAC_SWITCHPTH"))
    )
    (comp (ref "SW5")
      (value "TAC_SWITCHPTH")
      (footprint "eagle-import:TACTILE-PTH")
      (libsource (lib "eagle-import") (part "TAC_SWITCHPTH"))
    )
    (comp (ref "SW6")
      (value "TAC_SWITCHPTH")
      (footprint "eagle-import:TACTILE-PTH")
      (libsource (lib "eagle-import") (part "TAC_SWITCHPTH"))
    )
    (comp (ref "C1")
      (value "22u")
      (footprint "eagle-import:C1206")
      (libsource (lib "eagle-import") (part "C-USC1206"))
    )
    (comp (ref "C2")
      (value "22u")
      (footprint "eagle-import:C1206")
      (libsource (lib "eagle-import") (part "C-USC1206"))
    )
    (comp (ref "C10")
      (value "22u")
      (footprint "eagle-import:C1206")
      (libsource (lib "eagle-import") (part "C-USC1206"))
    )
    (comp (ref "C15")
      (value "100n")
      (footprint "eagle-import:C0402")
      (libsource (lib "eagle-import") (part "C-USC0402"))
    )
    (comp (ref "C17")
      (value "22u")
      (footprint "eagle-import:C1206")
      (libsource (lib "eagle-import") (part "C-USC1206"))
    )
    (comp (ref "C19")
      (value "22u")
      (footprint "eagle-import:C1206")
      (libsource (lib "eagle-import") (part "C-USC1206"))
    )
    (comp (ref "C20")
      (value "22u")
      (footprint "eagle-import:C1206")
      (libsource (lib "eagle-import") (part "C-USC1206"))
    )
    (comp (ref "C21")
      (value "22u")
      (footprint "eagle-import:C1206")
      (libsource (lib "eagle-import") (part "C-USC1206"))
    )
    (comp (ref "C23")
      (value "22u")
      (footprint "eagle-import:C1206")
      (libsource (lib "eagle-import") (part "C-USC1206"))
    )
    (comp (ref "C25")
      (value "22u")
      (footprint "eagle-import:C1206")
      (libsource (lib "eagle-import") (part "C-USC1206"))
    )
    (comp (ref "C41")
      (value "1u")
      (footprint "eagle-import:C0402")
      (libsource (lib "eagle-import") (part "C-USC0402"))
    )
    (comp (ref "D1")
      (value "1N5819HW")
      (footprint "eagle-import:SOD123")
      (libsource (lib "eagle-import") (part "DIODE-SOD123"))
    )
    (comp (ref "D2")
      (value "1N5819HW")
      (footprint "eagle-import:SOD123")
      (libsource (lib "eagle-import") (part "DIODE-SOD123"))
    )
    (comp (ref "H3")
      (value "MOUNT-HOLE3.0TINY")
      (footprint "eagle-import:3,0TINY")
      (libsource (lib "eagle-import") (part "MOUNT-HOLE3.0TINY"))
    )
    (comp (ref "IC2")
      (value "ROF-78E3.3-0.5SMD")
      (footprint "eagle-import:ROF78EXX-0.5SMD")
      (libsource (lib "eagle-import") (part "ROF-78EXX-0.55SMD"))
    )
    (comp (ref "IC7")
      (value "LD2981ABU33")
      (footprint "eagle-import:SOT89")
      (libsource (lib "eagle-import") (part "LD2981ABU"))
    )
    (comp (ref "IC11")
      (value "LM4040B25")
      (footprint "eagle-import:DBZ_R-PDSO-G3")
      (libsource (lib "eagle-import") (part "LM4041DBZB12"))
    )
    (comp (ref "JP5")
      (value "M05X2SMD")
      (footprint "eagle-import:2X5-SMD")
      (libsource (lib "eagle-import") (part "M05X2SMD"))
    )
    (comp (ref "L1")
      (value "WE-CBF_0603")
      (footprint "eagle-import:0603")
      (libsource (lib "eagle-import") (part "WE-CBF_0603"))
    )
    (comp (ref "L3")
      (value "33u")
      (footprint "eagle-import:L2012C")
      (libsource (lib "eagle-import") (part "L-USL2012C"))
    )
    (comp (ref "L4")
      (value "WE-CBF_0603")
      (footprint "eagle-import:0603")
      (libsource (lib "eagle-import") (part "WE-CBF_0603"))
    )
    (comp (ref "L5")
      (value "WE-CBF_0603")
      (footprint "eagle-import:0603")
      (libsource (lib "eagle-import") (part "WE-CBF_0603"))
    )
    (comp (ref "R33")
      (value "10k")
      (footprint "eagle-import:R0402")
      (libsource (lib "eagle-import") (part "R-US_R0402"))
    )
    (comp (ref "D3")
      (value "1N4148")
      (footprint "eagle-import:SOD523")
      (libsource (lib "eagle-import") (part "DIODE-SOD523"))
    )
    (comp (ref "D4")
      (value "1N4148")
      (footprint "eagle-import:SOD523")
      (libsource (lib "eagle-import") (part "DIODE-SOD523"))
    )
    (comp (ref "D5")
      (value "1N4148")
      (footprint "eagle-import:SOD523")
      (libsource (lib "eagle-import") (part "DIODE-SOD523"))
    )
    (comp (ref "D6")
      (value "1N4148")
      (footprint "eagle-import:SOD523")
      (libsource (lib "eagle-import") (part "DIODE-SOD523"))
    )
    (comp (ref "D7")
      (value "1N4148")
      (footprint "eagle-import:SOD523")
      (libsource (lib "eagle-import") (part "DIODE-SOD523"))
    )
    (comp (ref "D8")
      (value "1N4148")
      (footprint "eagle-import:SOD523")
      (libsource (lib "eagle-import") (part "DIODE-SOD523"))
    )
    (comp (ref "D9")
      (value "BAT54S")
      (footprint "eagle-import:SOT23")
      (libsource (lib "eagle-import") (part "DIODE_2CACA-SOT23"))
    )
    (comp (ref "J7")
      (value "PJ301_THONKICONN6")
      (footprint "eagle-import:WQP_PJ_301M6")
      (libsource (lib "eagle-import") (part "PJ301_THONKICONN6"))
    )
    (comp (ref "J8")
      (value "PJ301_THONKICONN6")
      (footprint "eagle-import:WQP_PJ_301M6")
      (libsource (lib "eagle-import") (part "PJ301_THONKICONN6"))
    )
    (comp (ref "J9")
      (value "PJ301_THONKICONN6")
      (footprint "eagle-import:WQP_PJ_301M6")
      (libsource (lib "eagle-import") (part "PJ301_THONKICONN6"))
    )
    (comp (ref "J10")
      (value "PJ301_THONKICONN6")
      (footprint "eagle-import:WQP_PJ_301M6")
      (libsource (lib "eagle-import") (part "PJ301_THONKICONN6"))
    )
    (comp (ref "J11")
      (value "PJ301_THONKICONN6")
      (footprint "eagle-import:WQP_PJ_301M6")
      (libsource (lib "eagle-import") (part "PJ301_THONKICONN6"))
    )
    (comp (ref "J12")
      (value "PJ301_THONKICONN6")
      (footprint "eagle-import:WQP_PJ_301M6")
      (libsource (lib "eagle-import") (part "PJ301_THONKICONN6"))
    )
    (comp (ref "Q2")
      (value "MMBT3904")
      (footprint "eagle-import:SOT23-BEC")
      (libsource (lib "eagle-import") (part "-NPN-SOT23-BECMMBT3904LT1"))
    )
    (comp (ref "Q3")
      (value "MMBT3904")
      (footprint "eagle-import:SOT23-BEC")
      (libsource (lib "eagle-import") (part "-NPN-SOT23-BECMMBT3904LT1"))
    )
    (comp (ref "Q4")
      (value "MMBT3904")
      (footprint "eagle-import:SOT23-BEC")
      (libsource (lib "eagle-import") (part "-NPN-SOT23-BECMMBT3904LT1"))
    )
    (comp (ref "Q5")
      (value "MMBT3904")
      (footprint "eagle-import:SOT23-BEC")
      (libsource (lib "eagle-import") (part "-NPN-SOT23-BECMMBT3904LT1"))
    )
    (comp (ref "Q6")
      (value "MMBT3904")
      (footprint "eagle-import:SOT23-BEC")
      (libsource (lib "eagle-import") (part "-NPN-SOT23-BECMMBT3904LT1"))
    )
    (comp (ref "Q7")
      (value "MMBT3904")
      (footprint "eagle-import:SOT23-BEC")
      (libsource (lib "eagle-import") (part "-NPN-SOT23-BECMMBT3904LT1"))
    )
    (comp (ref "R60")
      (value "10k")
      (footprint "eagle-import:R0402")
      (libsource (lib "eagle-import") (part "R-US_R0402"))
    )
    (comp (ref "R61")
      (value "10k")
      (footprint "eagle-import:R0402")
      (libsource (lib "eagle-import") (part "R-US_R0402"))
    )
    (comp (ref "R62")
      (value "10k")
      (footprint "eagle-import:R0402")
      (libsource (lib "eagle-import") (part "R-US_R0402"))
    )
    (comp (ref "R63")
      (value "10k")
      (footprint "eagle-import:R0402")
      (libsource (lib "eagle-import") (part "R-US_R0402"))
    )
    (comp (ref "R64")
      (value "10k")
      (footprint "eagle-import:R0402")
      (libsource (lib "eagle-import") (part "R-US_R0402"))
    )
    (comp (ref "R65")
      (value "10k")
      (footprint "eagle-import:R0402")
      (libsource (lib "eagle-import") (part "R-US_R0402"))
    )
    (comp (ref "R66")
      (value "100k")
      (footprint "eagle-import:R0402")
      (libsource (lib "eagle-import") (part "R-US_R0402"))
    )
    (comp (ref "R67")
      (value "100k")
      (footprint "eagle-import:R0402")
      (libsource (lib "eagle-import") (part "R-US_R0402"))
    )
    (comp (ref "R68")
      (value "100k")
      (footprint "eagle-import:R0402")
      (libsource (lib "eagle-import") (part "R-US_R0402"))
    )
    (comp (ref "R69")
      (value "100k")
      (footprint "eagle-import:R0402")
      (libsource (lib "eagle-import") (part "R-US_R0402"))
    )
    (comp (ref "R70")
      (value "100k")
      (footprint "eagle-import:R0402")
      (libsource (lib "eagle-import") (part "R-US_R0402"))
    )
    (comp (ref "R71")
      (value "100k")
      (footprint "eagle-import:R0402")
      (libsource (lib "eagle-import") (part "R-US_R0402"))
    )
    (comp (ref "R72")
      (value "100k")
      (footprint "eagle-import:R0402")
      (libsource (lib "eagle-import") (part "R-US_R0402"))
    )
    (comp (ref "R73")
      (value "100k")
      (footprint "eagle-import:R0402")
      (libsource (lib "eagle-import") (part "R-US_R0402"))
    )
    (comp (ref "R74")
      (value "100k")
      (footprint "eagle-import:R0402")
      (libsource (lib "eagle-import") (part "R-US_R0402"))
    )
    (comp (ref "R75")
      (value "100k")
      (footprint "eagle-import:R0402")
      (libsource (lib "eagle-import") (part "R-US_R0402"))
    )
    (comp (ref "R76")
      (value "100k")
      (footprint "eagle-import:R0402")
      (libsource (lib "eagle-import") (part "R-US_R0402"))
    )
    (comp (ref "R77")
      (value "100k")
      (footprint "eagle-import:R0402")
      (libsource (lib "eagle-import") (part "R-US_R0402"))
    )
  )
  (nets
    (net (code "1") (name "+3V3") (class "Default")
      (node (ref "C10") (pin "1") (pinfunction "1_1") (pintype "passive"))
      (node (ref "C11") (pin "1") (pinfunction "1_1") (pintype "passive"))
      (node (ref "C14") (pin "1") (pinfunction "1_1") (pintype "passive"))
      (node (ref "C15") (pin "1") (pinfunction "1_1") (pintype "passive"))
      (node (ref "C9") (pin "1") (pinfunction "1_1") (pintype "passive"))
      (node (ref "D9") (pin "2") (pinfunction "C_2") (pintype "passive"))
      (node (ref "IC2") (pin "3") (pinfunction "VO_3") (pintype "passive"))
      (node (ref "IC5") (pin "1") (pinfunction "VBAT_1") (pintype "power_in"))
      (node (ref "IC5") (pin "19") (pinfunction "VDD_2_19") (pintype "power_in"))
      (node (ref "IC5") (pin "64") (pinfunction "VDD_1_64") (pintype "power_in"))
      (node (ref "L2") (pin "2") (pinfunction "2_2") (pintype "passive"))
      (node (ref "LED10") (pin "A") (pinfunction "A_A") (pintype "bidirectional"))
      (node (ref "LED11") (pin "A") (pinfunction "A_A") (pintype "bidirectional"))
      (node (ref "LED12") (pin "A") (pinfunction "A_A") (pintype "bidirectional"))
      (node (ref "LED7") (pin "A") (pinfunction "A_A") (pintype "bidirectional"))
      (node (ref "LED8") (pin "A") (pinfunction "A_A") (pintype "bidirectional"))
      (node (ref "LED9") (pin "A") (pinfunction "A_A") (pintype "bidirectional"))
      (node (ref "R12") (pin "2") (pinfunction "2_2") (pintype "passive"))
    )
    (net (code "2") (name "+3V3_A") (class "Default")
      (node (ref "C12") (pin "1") (pinfunction "1_1") (pintype "passive"))
      (node (ref "C13") (pin "1") (pinfunction "1_1") (pintype "passive"))
      (node (ref "C16") (pin "1") (pinfunction "1_1") (pintype "passive"))
      (node (ref "C18") (pin "1") (pinfunction "1_1") (pintype "passive"))
      (node (ref "C20") (pin "1") (pinfunction "1_1") (pintype "passive"))
      (node (ref "C22") (pin "1") (pinfunction "1_1") (pintype "passive"))
      (node (ref "C24") (pin "1") (pinfunction "1_1") (pintype "passive"))
      (node (ref "C26") (pin "1") (pinfunction "1_1") (pintype "passive"))
      (node (ref "C30") (pin "1") (pinfunction "1_1") (pintype "passive"))
      (node (ref "C33") (pin "1") (pinfunction "1_1") (pintype "passive"))
      (node (ref "C34") (pin "1") (pinfunction "1_1") (pintype "passive"))
      (node (ref "C5") (pin "1") (pinfunction "1_1") (pintype "passive"))
      (node (ref "C7") (pin "1") (pinfunction "1_1") (pintype "passive"))
      (node (ref "IC10") (pin "8") (pinfunction "V+_8") (pintype "power_in"))
      (node (ref "IC3") (pin "16") (pinfunction "VCC_16") (pintype "power_in"))
      (node (ref "IC4") (pin "2") (pinfunction "AVDD_2") (pintype "power_in"))
      (node (ref "IC5") (pin "13") (pinfunction "VDDA_13") (pintype "power_in"))
      (node (ref "IC5") (pin "17") (pinfunction "VREF+_17") (pintype "power_in"))
      (node (ref "IC5") (pin "32") (pinfunction "VDDSD_32") (pintype "power_in"))
      (node (ref "IC5") (pin "33") (pinfunction "VREFSD+_33") (pintype "power_in"))
      (node (ref "IC6") (pin "16") (pinfunction "VCC_16") (pintype "power_in"))
      (node (ref "IC7") (pin "1") (pinfunction "VO_1") (pintype "passive"))
      (node (ref "IC8") (pin "8") (pinfunction "V+_8") (pintype "power_in"))
      (node (ref "IC9") (pin "8") (pinfunction "V+_8") (pintype "power_in"))
      (node (ref "R78") (pin "3") (pinfunction "E_3") (pintype "passive"))
      (node (ref "R79") (pin "3") (pinfunction "E_3") (pintype "passive"))
      (node (ref "R80") (pin "3") (pinfunction "E_3") (pintype "passive"))
      (node (ref "R81") (pin "3") (pinfunction "E_3") (pintype "passive"))
      (node (ref "R82") (pin "3") (pinfunction "E_3") (pintype "passive"))
      (node (ref "R83") (pin "3") (pinfunction "E_3") (pintype "passive"))
      (node (ref "R84") (pin "P$1") (pinfunction "E_P$1") (pintype "passive"))
      (node (ref "R85") (pin "P$1") (pinfunction "E_P$1") (pintype "passive"))
      (node (ref "R86") (pin "P$1") (pinfunction "E_P$1") (pintype "passive"))
      (node (ref "R87") (pin "P$1") (pinfunction "E_P$1") (pintype "passive"))
      (node (ref "R88") (pin "P$1") (pinfunction "E_P$1") (pintype "passive"))
      (node (ref "R89") (pin "P$1") (pinfunction "E_P$1") (pintype "passive"))
    )
    (net (code "3") (name "ADC_CV_1") (class "Default")
      (node (ref "C35") (pin "2") (pinfunction "2_2") (pintype "passive"))
      (node (ref "IC10") (pin "7") (pinfunction "OUT_7") (pintype "output"))
      (node (ref "IC5") (pin "34") (pinfunction "PB14/SPI2_MISO/I2S2_MCK/USART3_RTS/SDADC3_AIN8P_34") (pintype "bidirectional"))
      (node (ref "R16") (pin "1") (pinfunction "1_1") (pintype "passive"))
    )
    (net (code "4") (name "ADC_CV_2") (class "Default")
      (node (ref "C32") (pin "2") (pinfunction "2_2") (pintype "passive"))
      (node (ref "IC10") (pin "1") (pinfunction "OUT_1") (pintype "output"))
      (node (ref "IC5") (pin "35") (pinfunction "PB15/SPI2_MOSI/I2S2_SD/SDADC3_AIN7P/SDADC3_AIN8M_35") (pintype "bidirectional"))
      (node (ref "R14") (pin "1") (pinfunction "1_1") (pintype "passive"))
    )
    (net (code "5") (name "ADC_CV_3") (class "Default")
      (node (ref "C31") (pin "2") (pinfunction "2_2") (pintype "passive"))
      (node (ref "IC5") (pin "29") (pinfunction "PE8/SDADC1_AIN8P/SDADC2_AIN8P_29") (pintype "bidirectional"))
      (node (ref "IC9") (pin "7") (pinfunction "OUT_7") (pintype "output"))
      (node (ref "R13") (pin "1") (pinfunction "1_1") (pintype "passive"))
    )
    (net (code "6") (name "ADC_CV_4") (class "Default")
      (node (ref "C29") (pin "2") (pinfunction "2_2") (pintype "passive"))
      (node (ref "IC5") (pin "30") (pinfunction "PE9/SDADC1_AIN7P/SDADC1_AIN8M/SDADC2_AIN7P/SDADC2_AIN8M_30") (pintype "bidirectional"))
      (node (ref "IC9") (pin "1") (pinfunction "OUT_1") (pintype "output"))
      (node (ref "R15") (pin "1") (pinfunction "1_1") (pintype "passive"))
    )
    (net (code "7") (name "ADC_CV_5") (class "Default")
      (node (ref "C27") (pin "2") (pinfunction "2_2") (pintype "passive"))
      (node (ref "IC5") (pin "27") (pinfunction "PB1/TIM3_CH4/ADC_IN9/SDADC1_AIN5P/SDADC1_AIN6M_27") (pintype "bidirectional"))
      (node (ref "IC8") (pin "7") (pinfunction "OUT_7") (pintype "output"))
      (node (ref "R19") (pin "1") (pinfunction "1_1") (pintype "passive"))
    )
    (net (code "8") (name "ADC_CV_6") (class "Default")
      (node (ref "C28") (pin "2") (pinfunction "2_2") (pintype "passive"))
      (node (ref "IC5") (pin "26") (pinfunction "PB0/SPI1_MOSI/I2S1_SD/TIM3_CH3/ADC_IN8/SDADC1_AIN6P_26") (pintype "bidirectional"))
      (node (ref "IC8") (pin "1") (pinfunction "OUT_1") (pintype "output"))
      (node (ref "R20") (pin "1") (pinfunction "1_1") (pintype "passive"))
    )
    (net (code "9") (name "ADC_SHAPE") (class "Default")
      (node (ref "IC3") (pin "3") (pinfunction "X_3") (pintype "bidirectional"))
      (node (ref "IC5") (pin "22") (pinfunction "PA6/SPI1_MISO/I2S1_MCK/TIM3_CH1/ADC_IN6/DAC2_OUT1_22") (pintype "bidirectional"))
    )
    (net (code "10") (name "ADC_TIME_LEVEL") (class "Default")
      (node (ref "IC5") (pin "23") (pinfunction "PA7/SPI1_MOSI/I2S1_SD/TIM3_CH2/ADC_IN7_23") (pintype "bidirectional"))
      (node (ref "IC6") (pin "3") (pinfunction "X_3") (pintype "bidirectional"))
    )
    (net (code "11") (name "AREF_-2.5") (class "Default")
      (node (ref "C41") (pin "1") (pinfunction "1_1") (pintype "passive"))
      (node (ref "IC11") (pin "2") (pinfunction "A_2") (pintype "passive"))
      (node (ref "R21") (pin "2") (pinfunction "2_2") (pintype "passive"))
      (node (ref "R22") (pin "2") (pinfunction "2_2") (pintype "passive"))
      (node (ref "R23") (pin "2") (pinfunction "2_2") (pintype "passive"))
      (node (ref "R24") (pin "2") (pinfunction "2_2") (pintype "passive"))
      (node (ref "R26") (pin "2") (pinfunction "2_2") (pintype "passive"))
      (node (ref "R29") (pin "2") (pinfunction "2_2") (pintype "passive"))
      (node (ref "R33") (pin "2") (pinfunction "2_2") (pintype "passive"))
    )
    (net (code "12") (name "AREF_2.5") (class "Default")
      (node (ref "IC4") (pin "7") (pinfunction "VREF_7") (pintype "input"))
      (node (ref "R40") (pin "2") (pinfunction "2_2") (pintype "passive"))
    )
    (net (code "13") (name "DAC_1") (class "Default")
      (node (ref "IC4") (pin "10") (pinfunction "VOUTD_10") (pintype "output"))
      (node (ref "R52") (pin "2") (pinfunction "2_2") (pintype "passive"))
    )
    (net (code "14") (name "DAC_2") (class "Default")
      (node (ref "IC4") (pin "11") (pinfunction "VOUTB_11") (pintype "output"))
      (node (ref "R51") (pin "2") (pinfunction "2_2") (pintype "passive"))
    )
    (net (code "15") (name "DAC_3") (class "Default")
      (node (ref "IC4") (pin "6") (pinfunction "VOUTG_6") (pintype "output"))
      (node (ref "R53") (pin "2") (pinfunction "2_2") (pintype "passive"))
    )
    (net (code "16") (name "DAC_4") (class "Default")
      (node (ref "IC4") (pin "4") (pinfunction "VOUTC_4") (pintype "output"))
      (node (ref "R49") (pin "2") (pinfunction "2_2") (pintype "passive"))
    )
    (net (code "17") (name "DAC_5") (class "Default")
      (node (ref "IC4") (pin "3") (pinfunction "VOUTA_3") (pintype "output"))
      (node (ref "R50") (pin "2") (pinfunction "2_2") (pintype "passive"))
    )
    (net (code "18") (name "DAC_6") (class "Default")
      (node (ref "IC4") (pin "5") (pinfunction "VOUTE_5") (pintype "output"))
      (node (ref "R47") (pin "2") (pinfunction "2_2") (pintype "passive"))
    )
    (net (code "19") (name "DAC_MOSI") (class "Default")
      (node (ref "IC4") (pin "13") (pinfunction "DIN_13") (pintype "input"))
      (node (ref "IC5") (pin "53") (pinfunction "PC12/SPI3_MOSI/I2S3_SD/USART3_CK_53") (pintype "bidirectional"))
    )
    (net (code "20") (name "DAC_SCK") (class "Default")
      (node (ref "IC4") (pin "14") (pinfunction "SCLK_14") (pintype "input"))
      (node (ref "IC5") (pin "51") (pinfunction "PC10/SPI3_SCK/I2S3_CK/USART3_TX_51") (pintype "bidirectional"))
    )
    (net (code "21") (name "DAC_SS") (class "Default")
      (node (ref "IC4") (pin "1") (pinfunction "~{SYNC}_1") (pintype "input"))
      (node (ref "IC5") (pin "50") (pinfunction "PA15/SPI1_NSS/I2S1_WS/SPI3_NSS/I2S3_WS/I2C1_SCL/TIM2_CH1_ETR/JTDI_50") (pintype "bidirectional"))
    )
    (net (code "22") (name "GATE_1") (class "Default")
      (node (ref "IC5") (pin "44") (pinfunction "PA11/SPI2_NSS/I2S2_WS/SPI1_NSS/I2S1_WS/USART1_CTS/CAN_RX/TIM4_CH1/TIM5_CH2_44") (pintype "bidirectional"))
      (node (ref "Q7") (pin "C") (pinfunction "C_C") (pintype "passive"))
    )
    (net (code "23") (name "GATE_2") (class "Default")
      (node (ref "IC5") (pin "43") (pinfunction "PA10/SPI2_MOSI/I2S2_SD/I2C2_SDA/USART1_RX/TIM2_CH4_43") (pintype "bidirectional"))
      (node (ref "Q3") (pin "C") (pinfunction "C_C") (pintype "passive"))
    )
    (net (code "24") (name "GATE_3") (class "Default")
      (node (ref "IC5") (pin "42") (pinfunction "PA9/SPI_MISO/I2S2_MCK/I2C2_SCL/USART1_TX/TIM2_CH3_42") (pintype "bidirectional"))
      (node (ref "Q6") (pin "C") (pinfunction "C_C") (pintype "passive"))
    )
    (net (code "25") (name "GATE_4") (class "Default")
      (node (ref "IC5") (pin "41") (pinfunction "PA8/SPI2_SCK/I2S2_CK/I2C2_SMBA/USART1_CK/TIM5_CH1_41") (pintype "bidirectional"))
      (node (ref "Q4") (pin "C") (pinfunction "C_C") (pintype "passive"))
    )
    (net (code "26") (name "GATE_5") (class "Default")
      (node (ref "IC5") (pin "39") (pinfunction "PC8/SPI1_MISO/I2S1_MCK/TIM3_CH3_39") (pintype "bidirectional"))
      (node (ref "Q5") (pin "C") (pinfunction "C_C") (pintype "passive"))
    )
    (net (code "27") (name "GATE_6") (class "Default")
      (node (ref "IC5") (pin "38") (pinfunction "PC7/SPI1_SCK/I2S1_CK/TIM3_CH2_38") (pintype "bidirectional"))
      (node (ref "Q2") (pin "C") (pinfunction "C_C") (pintype "passive"))
    )
    (net (code "28") (name "GND") (class "Default")
      (node (ref "C1") (pin "1") (pinfunction "1_1") (pintype "passive"))
      (node (ref "C10") (pin "2") (pinfunction "2_2") (pintype "passive"))
      (node (ref "C11") (pin "2") (pinfunction "2_2") (pintype "passive"))
      (node (ref "C12") (pin "2") (pinfunction "2_2") (pintype "passive"))
      (node (ref "C13") (pin "2") (pinfunction "2_2") (pintype "passive"))
      (node (ref "C14") (pin "2") (pinfunction "2_2") (pintype "passive"))
      (node (ref "C15") (pin "2") (pinfunction "2_2") (pintype "passive"))
      (node (ref "C16") (pin "2") (pinfunction "2_2") (pintype "passive"))
      (node (ref "C17") (pin "2") (pinfunction "2_2") (pintype "passive"))
      (node (ref "C18") (pin "2") (pinfunction "2_2") (pintype "passive"))
      (node (ref "C19") (pin "2") (pinfunction "2_2") (pintype "passive"))
      (node (ref "C2") (pin "1") (pinfunction "1_1") (pintype "passive"))
      (node (ref "C20") (pin "2") (pinfunction "2_2") (pintype "passive"))
      (node (ref "C21") (pin "2") (pinfunction "2_2") (pintype "passive"))
      (node (ref "C22") (pin "2") (pinfunction "2_2") (pintype "passive"))
      (node (ref "C23") (pin "2") (pinfunction "2_2") (pintype "passive"))
      (node (ref "C24") (pin "2") (pinfunction "2_2") (pintype "passive"))
      (node (ref "C25") (pin "2") (pinfunction "2_2") (pintype "passive"))
      (node (ref "C26") (pin "2") (pinfunction "2_2") (pintype "passive"))
      (node (ref "C3") (pin "1") (pinfunction "1_1") (pintype "passive"))
      (node (ref "C30") (pin "2") (pinfunction "2_2") (pintype "passive"))
      (node (ref "C33") (pin "2") (pinfunction "2_2") (pintype "passive"))
      (node (ref "C34") (pin "2") (pinfunction "2_2") (pintype "passive"))
      (node (ref "C36") (pin "2") (pinfunction "2_2") (pintype "passive"))
      (node (ref "C37") (pin "2") (pinfunction "2_2") (pintype "passive"))
      (node (ref "C38") (pin "2") (pinfunction "2_2") (pintype "passive"))
      (node (ref "C39") (pin "2") (pinfunction "2_2") (pintype "passive"))
      (node (ref "C4") (pin "1") (pinfunction "1_1") (pintype "passive"))
      (node (ref "C40") (pin "2") (pinfunction "2_2") (pintype "passive"))
      (node (ref "C41") (pin "2") (pinfunction "2_2") (pintype "passive"))
      (node (ref "C42") (pin "2") (pinfunction "2_2") (pintype "passive"))
      (node (ref "C43") (pin "2") (pinfunction "2_2") (pintype "passive"))
      (node (ref "C5") (pin "2") (pinfunction "2_2") (pintype "passive"))
      (node (ref "C50") (pin "2") (pinfunction "2_2") (pintype "passive"))
      (node (ref "C51") (pin "1") (pinfunction "1_1") (pintype "passive"))
      (node (ref "C52") (pin "2") (pinfunction "2_2") (pintype "passive"))
      (node (ref "C53") (pin "1") (pinfunction "1_1") (pintype "passive"))
      (node (ref "C54") (pin "2") (pinfunction "2_2") (pintype "passive"))
      (node (ref "C55") (pin "1") (pinfunction "1_1") (pintype "passive"))
      (node (ref "C6") (pin "2") (pinfunction "2_2") (pintype "passive"))
      (node (ref "C7") (pin "2") (pinfunction "2_2") (pintype "passive"))
      (node (ref "C8") (pin "2") (pinfunction "2_2") (pintype "passive"))
      (node (ref "C9") (pin "2") (pinfunction "2_2") (pintype "passive"))
      (node (ref "D3") (pin "A") (pinfunction "A_A") (pintype "passive"))
      (node (ref "D4") (pin "A") (pinfunction "A_A") (pintype "passive"))
      (node (ref "D5") (pin "A") (pinfunction "A_A") (pintype "passive"))
      (node (ref "D6") (pin "A") (pinfunction "A_A") (pintype "passive"))
      (node (ref "D7") (pin "A") (pinfunction "A_A") (pintype "passive"))
      (node (ref "D8") (pin "A") (pinfunction "A_A") (pintype "passive"))
      (node (ref "D9") (pin "1") (pinfunction "A_1") (pintype "passive"))
      (node (ref "IC1") (pin "1") (pinfunction "GND_1") (pintype "bidirectional"))
      (node (ref "IC1") (pin "21") (pinfunction "BLANK_21") (pintype "bidirectional"))
      (node (ref "IC10") (pin "3") (pinfunction "+IN_3") (pintype "input"))
      (node (ref "IC10") (pin "4") (pinfunction "V-_4") (pintype "power_in"))
      (node (ref "IC10") (pin "5") (pinfunction "+IN_5") (pintype "input"))
      (node (ref "IC11") (pin "1") (pinfunction "C_1") (pintype "passive"))
      (node (ref "IC2") (pin "2") (pinfunction "GND_2") (pintype "passive"))
      (node (ref "IC3") (pin "6") (pinfunction "INH_6") (pintype "input"))
      (node (ref "IC3") (pin "7") (pinfunction "VEE_7") (pintype "power_in"))
      (node (ref "IC3") (pin "8") (pinfunction "GND_8") (pintype "power_in"))
      (node (ref "IC4") (pin "12") (pinfunction "GND_12") (pintype "passive"))
      (node (ref "IC5") (pin "12") (pinfunction "VSSA_12") (pintype "power_in"))
      (node (ref "IC5") (pin "31") (pinfunction "VSSSD/VREFSD-_31") (pintype "power_in"))
      (node (ref "IC5") (pin "60") (pinfunction "BOOT0_60") (pintype "bidirectional"))
      (node (ref "IC5") (pin "63") (pinfunction "VSS_1_63") (pintype "power_in"))
      (node (ref "IC6") (pin "6") (pinfunction "INH_6") (pintype "input"))
      (node (ref "IC6") (pin "7") (pinfunction "VEE_7") (pintype "power_in"))
      (node (ref "IC6") (pin "8") (pinfunction "GND_8") (pintype "power_in"))
      (node (ref "IC7") (pin "2") (pinfunction "GND_2") (pintype "passive"))
      (node (ref "IC8") (pin "3") (pinfunction "+IN_3") (pintype "input"))
      (node (ref "IC8") (pin "4") (pinfunction "V-_4") (pintype "power_in"))
      (node (ref "IC8") (pin "5") (pinfunction "+IN_5") (pintype "input"))
      (node (ref "IC9") (pin "3") (pinfunction "+IN_3") (pintype "input"))
      (node (ref "IC9") (pin "4") (pinfunction "V-_4") (pintype "power_in"))
      (node (ref "IC9") (pin "5") (pinfunction "+IN_5") (pintype "input"))
      (node (ref "J1") (pin "P1") (pinfunction "1_P1") (pintype "passive"))
      (node (ref "J10") (pin "P1") (pinfunction "1_P1") (pintype "passive"))
      (node (ref "J11") (pin "P1") (pinfunction "1_P1") (pintype "passive"))
      (node (ref "J12") (pin "P1") (pinfunction "1_P1") (pintype "passive"))
      (node (ref "J13") (pin "P1") (pinfunction "1_P1") (pintype "passive"))
      (node (ref "J13") (pin "P2") (pinfunction "2_P2") (pintype "passive"))
      (node (ref "J14") (pin "P1") (pinfunction "1_P1") (pintype "passive"))
      (node (ref "J14") (pin "P2") (pinfunction "2_P2") (pintype "passive"))
      (node (ref "J15") (pin "P1") (pinfunction "1_P1") (pintype "passive"))
      (node (ref "J15") (pin "P2") (pinfunction "2_P2") (pintype "passive"))
      (node (ref "J16") (pin "P1") (pinfunction "1_P1") (pintype "passive"))
      (node (ref "J16") (pin "P2") (pinfunction "2_P2") (pintype "passive"))
      (node (ref "J17") (pin "P1") (pinfunction "1_P1") (pintype "passive"))
      (node (ref "J17") (pin "P2") (pinfunction "2_P2") (pintype "passive"))
      (node (ref "J18") (pin "P1") (pinfunction "1_P1") (pintype "passive"))
      (node (ref "J18") (pin "P2") (pinfunction "2_P2") (pintype "passive"))
      (node (ref "J2") (pin "P1") (pinfunction "1_P1") (pintype "passive"))
      (node (ref "J3") (pin "P1") (pinfunction "1_P1") (pintype "passive"))
      (node (ref "J4") (pin "P1") (pinfunction "1_P1") (pintype "passive"))
      (node (ref "J5") (pin "P1") (pinfunction "1_P1") (pintype "passive"))
      (node (ref "J6") (pin "P1") (pinfunction "1_P1") (pintype "passive"))
      (node (ref "J7") (pin "P1") (pinfunction "1_P1") (pintype "passive"))
      (node (ref "J8") (pin "P1") (pinfunction "1_P1") (pintype "passive"))
      (node (ref "J9") (pin "P1") (pinfunction "1_P1") (pintype "passive"))
      (node (ref "JP3") (pin "1") (pinfunction "1_1") (pintype "passive"))
      (node (ref "JP4") (pin "1") (pinfunction "1_1") (pintype "passive"))
      (node (ref "JP5") (pin "3") (pinfunction "3_3") (pintype "passive"))
      (node (ref "JP5") (pin "4") (pinfunction "4_4") (pintype "passive"))
      (node (ref "JP5") (pin "5") (pinfunction "5_5") (pintype "passive"))
      (node (ref "JP5") (pin "6") (pinfunction "6_6") (pintype "passive"))
      (node (ref "JP5") (pin "7") (pinfunction "7_7") (pintype "passive"))
      (node (ref "JP5") (pin "8") (pinfunction "8_8") (pintype "passive"))
      (node (ref "JP6") (pin "1") (pinfunction "1_1") (pintype "passive"))
      (node (ref "Q1") (pin "2") (pinfunction "LID1_2") (pintype "power_in"))
      (node (ref "Q1") (pin "4") (pinfunction "LID2_4") (pintype "power_in"))
      (node (ref "Q2") (pin "E") (pinfunction "E_E") (pintype "passive"))
      (node (ref "Q3") (pin "E") (pinfunction "E_E") (pintype "passive"))
      (node (ref "Q4") (pin "E") (pinfunction "E_E") (pintype "passive"))
      (node (ref "Q5") (pin "E") (pinfunction "E_E") (pintype "passive"))
      (node (ref "Q6") (pin "E") (pinfunction "E_E") (pintype "passive"))
      (node (ref "Q7") (pin "E") (pinfunction "E_E") (pintype "passive"))
      (node (ref "R48") (pin "1") (pinfunction "1_1") (pintype "passive"))
      (node (ref "R54") (pin "2") (pinfunction "2_2") (pintype "passive"))
      (node (ref "R55") (pin "2") (pinfunction "2_2") (pintype "passive"))
      (node (ref "R56") (pin "2") (pinfunction "2_2") (pintype "passive"))
      (node (ref "R57") (pin "2") (pinfunction "2_2") (pintype "passive"))
      (node (ref "R58") (pin "2") (pinfunction "2_2") (pintype "passive"))
      (node (ref "R59") (pin "2") (pinfunction "2_2") (pintype "passive"))
      (node (ref "R6") (pin "2") (pinfunction "2_2") (pintype "passive"))
      (node (ref "R69") (pin "1") (pinfunction "1_1") (pintype "passive"))
      (node (ref "R70") (pin "1") (pinfunction "1_1") (pintype "passive"))
      (node (ref "R71") (pin "1") (pinfunction "1_1") (pintype "passive"))
      (node (ref "R72") (pin "1") (pinfunction "1_1") (pintype "passive"))
      (node (ref "R73") (pin "1") (pinfunction "1_1") (pintype "passive"))
      (node (ref "R74") (pin "1") (pinfunction "1_1") (pintype "passive"))
      (node (ref "R78") (pin "1") (pinfunction "A_1") (pintype "passive"))
      (node (ref "R78") (pin "E") (pinfunction "C_E") (pintype "passive"))
      (node (ref "R79") (pin "1") (pinfunction "A_1") (pintype "passive"))
      (node (ref "R79") (pin "E") (pinfunction "C_E") (pintype "passive"))
      (node (ref "R80") (pin "1") (pinfunction "A_1") (pintype "passive"))
      (node (ref "R80") (pin "E") (pinfunction "C_E") (pintype "passive"))
      (node (ref "R81") (pin "1") (pinfunction "A_1") (pintype "passive"))
      (node (ref "R81") (pin "E") (pinfunction "C_E") (pintype "passive"))
      (node (ref "R82") (pin "1") (pinfunction "A_1") (pintype "passive"))
      (node (ref "R82") (pin "E") (pinfunction "C_E") (pintype "passive"))
      (node (ref "R83") (pin "1") (pinfunction "A_1") (pintype "passive"))
      (node (ref "R83") (pin "E") (pinfunction "C_E") (pintype "passive"))
      (node (ref "R84") (pin "P$3") (pinfunction "A_P$3") (pintype "passive"))
      (node (ref "R85") (pin "P$3") (pinfunction "A_P$3") (pintype "passive"))
      (node (ref "R86") (pin "P$3") (pinfunction "A_P$3") (pintype "passive"))
      (node (ref "R87") (pin "P$3") (pinfunction "A_P$3") (pintype "passive"))
      (node (ref "R88") (pin "P$3") (pinfunction "A_P$3") (pintype "passive"))
      (node (ref "R89") (pin "P$3") (pinfunction "A_P$3") (pintype "passive"))
      (node (ref "SW1") (pin "1") (pinfunction "1_1") (pintype "passive"))
      (node (ref "SW1") (pin "2") (pinfunction "2_2") (pintype "passive"))
      (node (ref "SW2") (pin "1") (pinfunction "1_1") (pintype "passive"))
      (node (ref "SW2") (pin "2") (pinfunction "2_2") (pintype "passive"))
      (node (ref "SW3") (pin "1") (pinfunction "1_1") (pintype "passive"))
      (node (ref "SW3") (pin "2") (pinfunction "2_2") (pintype "passive"))
      (node (ref "SW4") (pin "1") (pinfunction "1_1") (pintype "passive"))
      (node (ref "SW4") (pin "2") (pinfunction "2_2") (pintype "passive"))
      (node (ref "SW5") (pin "1") (pinfunction "1_1") (pintype "passive"))
      (node (ref "SW5") (pin "2") (pinfunction "2_2") (pintype "passive"))
      (node (ref "SW6") (pin "1") (pinfunction "1_1") (pintype "passive"))
      (node (ref "SW6") (pin "2") (pinfunction "2_2") (pintype "passive"))
    )
    (net (code "29") (name "LEDS_SCK") (class "Default")
      (node (ref "IC1") (pin "3") (pinfunction "SCLK_3") (pintype "bidirectional"))
      (node (ref "IC5") (pin "58") (pinfunction "PB6/I2C1_SCL/USART1_TX/TIM4_CH1_58") (pintype "bidirectional"))
    )
    (net (code "30") (name "LEDS_SIN") (class "Default")
      (node (ref "IC1") (pin "2") (pinfunction "SIN_2") (pintype "bidirectional"))
      (node (ref "IC5") (pin "57") (pinfunction "PB5/SPI1_MOSI/I2S1_SD/SPI3_MOSI/I2S3_SD/I2C1_SMBAI/USART2_CK/TIM3_CH2_57") (pintype "bidirectional"))
    )
    (net (code "31") (name "LEDS_SS") (class "Default")
      (node (ref "IC1") (pin "4") (pinfunction "LAT_4") (pintype "bidirectional"))
      (node (ref "IC5") (pin "59") (pinfunction "PB7/I2C1_SDA/USART1_RX/TIM4_CH2_59") (pintype "bidirectional"))
    )
    (net (code "32") (name "LEFT_RX") (class "Default")
      (node (ref "IC5") (pin "62") (pinfunction "PB9/SPI2_NSS/I2S2_WS/I2C1_SDA/USART3_RX/CAN_TX/TIM4_CH4_62") (pintype "bidirectional"))
      (node (ref "R7") (pin "1") (pinfunction "1_1") (pintype "passive"))
    )
    (net (code "33") (name "LEFT_TX") (class "Default")
      (node (ref "IC5") (pin "61") (pinfunction "PB8/SPI2_SCK/I2S2_CK/I2C1_SCL/USART3_TX/CAN_RX/TIM4_CH3_61") (pintype "bidirectional"))
      (node (ref "R5") (pin "1") (pinfunction "1_1") (pintype "passive"))
    )
    (net (code "34") (name "NORMALIZATION_PROBE") (class "Default")
      (node (ref "D9") (pin "3") (pinfunction "AC_3") (pintype "passive"))
      (node (ref "IC5") (pin "40") (pinfunction "PC9/SPI1_MOSI/I2S1_SD/TIM3_CH4_40") (pintype "bidirectional"))
      (node (ref "R60") (pin "1") (pinfunction "1_1") (pintype "passive"))
      (node (ref "R61") (pin "1") (pinfunction "1_1") (pintype "passive"))
      (node (ref "R62") (pin "1") (pinfunction "1_1") (pintype "passive"))
      (node (ref "R63") (pin "1") (pinfunction "1_1") (pintype "passive"))
      (node (ref "R64") (pin "1") (pinfunction "1_1") (pintype "passive"))
      (node (ref "R65") (pin "1") (pinfunction "1_1") (pintype "passive"))
    )
    (net (code "35") (name "Net-(C3-Pad2)") (class "Default")
      (node (ref "C3") (pin "2") (pinfunction "2_2") (pintype "passive"))
      (node (ref "Q1") (pin "1") (pinfunction "1_1") (pintype "passive"))
      (node (ref "R9") (pin "2") (pinfunction "2_2") (pintype "passive"))
    )
    (net (code "36") (name "Net-(C17-Pad1)") (class "Default")
      (node (ref "C17") (pin "1") (pinfunction "1_1") (pintype "passive"))
      (node (ref "D2") (pin "C") (pinfunction "C_C") (pintype "passive"))
      (node (ref "L3") (pin "1") (pinfunction "1_1") (pintype "passive"))
      (node (ref "L4") (pin "2") (pinfunction "2_2") (pintype "passive"))
      (node (ref "L5") (pin "2") (pinfunction "2_2") (pintype "passive"))
    )
    (net (code "37") (name "Net-(D1-PadA)") (class "Default")
      (node (ref "D1") (pin "A") (pinfunction "A_A") (pintype "passive"))
      (node (ref "L1") (pin "2") (pinfunction "2_2") (pintype "passive"))
    )
    (net (code "38") (name "Net-(D1-PadC)") (class "Default")
      (node (ref "D1") (pin "C") (pinfunction "C_C") (pintype "passive"))
      (node (ref "JP5") (pin "10") (pinfunction "10_10") (pintype "passive"))
      (node (ref "JP5") (pin "9") (pinfunction "9_9") (pintype "passive"))
    )
    (net (code "39") (name "Net-(D2-PadA)") (class "Default")
      (node (ref "D2") (pin "A") (pinfunction "A_A") (pintype "passive"))
      (node (ref "JP5") (pin "1") (pinfunction "1_1") (pintype "passive"))
      (node (ref "JP5") (pin "2") (pinfunction "2_2") (pintype "passive"))
    )
    (net (code "40") (name "Net-(D3-PadC)") (class "Default")
      (node (ref "D3") (pin "C") (pinfunction "C_C") (pintype "passive"))
      (node (ref "Q7") (pin "B") (pinfunction "B_B") (pintype "passive"))
      (node (ref "R66") (pin "2") (pinfunction "2_2") (pintype "passive"))
      (node (ref "R69") (pin "2") (pinfunction "2_2") (pintype "passive"))
    )
    (net (code "41") (name "Net-(D4-PadC)") (class "Default")
      (node (ref "D4") (pin "C") (pinfunction "C_C") (pintype "passive"))
      (node (ref "Q5") (pin "B") (pinfunction "B_B") (pintype "passive"))
      (node (ref "R67") (pin "2") (pinfunction "2_2") (pintype "passive"))
      (node (ref "R70") (pin "2") (pinfunction "2_2") (pintype "passive"))
    )
    (net (code "42") (name "Net-(D5-PadC)") (class "Default")
      (node (ref "D5") (pin "C") (pinfunction "C_C") (pintype "passive"))
      (node (ref "Q6") (pin "B") (pinfunction "B_B") (pintype "passive"))
      (node (ref "R68") (pin "2") (pinfunction "2_2") (pintype "passive"))
      (node (ref "R71") (pin "2") (pinfunction "2_2") (pintype "passive"))
    )
    (net (code "43") (name "Net-(D6-PadC)") (class "Default")
      (node (ref "D6") (pin "C") (pinfunction "C_C") (pintype "passive"))
      (node (ref "Q2") (pin "B") (pinfunction "B_B") (pintype "passive"))
      (node (ref "R74") (pin "2") (pinfunction "2_2") (pintype "passive"))
      (node (ref "R75") (pin "2") (pinfunction "2_2") (pintype "passive"))
    )
    (net (code "44") (name "Net-(D7-PadC)") (class "Default")
      (node (ref "D7") (pin "C") (pinfunction "C_C") (pintype "passive"))
      (node (ref "Q3") (pin "B") (pinfunction "B_B") (pintype "passive"))
      (node (ref "R73") (pin "2") (pinfunction "2_2") (pintype "passive"))
      (node (ref "R77") (pin "2") (pinfunction "2_2") (pintype "passive"))
    )
    (net (code "45") (name "Net-(D8-PadC)") (class "Default")
      (node (ref "D8") (pin "C") (pinfunction "C_C") (pintype "passive"))
      (node (ref "Q4") (pin "B") (pinfunction "B_B") (pintype "passive"))
      (node (ref "R72") (pin "2") (pinfunction "2_2") (pintype "passive"))
      (node (ref "R76") (pin "2") (pinfunction "2_2") (pintype "passive"))
    )
    (net (code "46") (name "Net-(IC1-IREF)") (class "Default")
      (node (ref "IC1") (pin "23") (pinfunction "IREF_23") (pintype "bidirectional"))
      (node (ref "R6") (pin "1") (pinfunction "1_1") (pintype "passive"))
    )
    (net (code "47") (name "Net-(IC1-OUT2)") (class "Default")
      (node (ref "IC1") (pin "7") (pinfunction "OUT2_7") (pintype "bidirectional"))
      (node (ref "LED9") (pin "RED_C") (pinfunction "RED_RED_C") (pintype "bidirectional"))
    )
    (net (code "48") (name "Net-(IC1-OUT3)") (class "Default")
      (node (ref "IC1") (pin "8") (pinfunction "OUT3_8") (pintype "bidirectional"))
      (node (ref "LED9") (pin "GREEN_C") (pinfunction "GRN_GREEN_C") (pintype "bidirectional"))
    )
    (net (code "49") (name "Net-(IC1-OUT4)") (class "Default")
      (node (ref "IC1") (pin "9") (pinfunction "OUT4_9") (pintype "bidirectional"))
      (node (ref "LED7") (pin "GREEN_C") (pinfunction "GRN_GREEN_C") (pintype "bidirectional"))
    )
    (net (code "50") (name "Net-(IC1-OUT5)") (class "Default")
      (node (ref "IC1") (pin "10") (pinfunction "OUT5_10") (pintype "bidirectional"))
      (node (ref "LED7") (pin "RED_C") (pinfunction "RED_RED_C") (pintype "bidirectional"))
    )
    (net (code "51") (name "Net-(IC1-OUT6)") (class "Default")
      (node (ref "IC1") (pin "11") (pinfunction "OUT6_11") (pintype "bidirectional"))
      (node (ref "LED8") (pin "GREEN_C") (pinfunction "GRN_GREEN_C") (pintype "bidirectional"))
    )
    (net (code "52") (name "Net-(IC1-OUT7)") (class "Default")
      (node (ref "IC1") (pin "12") (pinfunction "OUT7_12") (pintype "bidirectional"))
      (node (ref "LED8") (pin "RED_C") (pinfunction "RED_RED_C") (pintype "bidirectional"))
    )
    (net (code "53") (name "Net-(IC1-OUT8)") (class "Default")
      (node (ref "IC1") (pin "13") (pinfunction "OUT8_13") (pintype "bidirectional"))
      (node (ref "LED10") (pin "GREEN_C") (pinfunction "GRN_GREEN_C") (pintype "bidirectional"))
    )
    (net (code "54") (name "Net-(IC1-OUT9)") (class "Default")
      (node (ref "IC1") (pin "14") (pinfunction "OUT9_14") (pintype "bidirectional"))
      (node (ref "LED10") (pin "RED_C") (pinfunction "RED_RED_C") (pintype "bidirectional"))
    )
    (net (code "55") (name "Net-(IC1-OUT10)") (class "Default")
      (node (ref "IC1") (pin "15") (pinfunction "OUT10_15") (pintype "bidirectional"))
      (node (ref "LED11") (pin "RED_C") (pinfunction "RED_RED_C") (pintype "bidirectional"))
    )
    (net (code "56") (name "Net-(IC1-OUT11)") (class "Default")
      (node (ref "IC1") (pin "16") (pinfunction "OUT11_16") (pintype "bidirectional"))
      (node (ref "LED11") (pin "GREEN_C") (pinfunction "GRN_GREEN_C") (pintype "bidirectional"))
    )
    (net (code "57") (name "Net-(IC1-OUT12)") (class "Default")
      (node (ref "IC1") (pin "17") (pinfunction "OUT12_17") (pintype "bidirectional"))
      (node (ref "LED12") (pin "RED_C") (pinfunction "RED_RED_C") (pintype "bidirectional"))
    )
    (net (code "58") (name "Net-(IC1-OUT13)") (class "Default")
      (node (ref "IC1") (pin "18") (pinfunction "OUT13_18") (pintype "bidirectional"))
      (node (ref "LED12") (pin "GREEN_C") (pinfunction "GRN_GREEN_C") (pintype "bidirectional"))
    )
    (net (code "59") (name "Net-(IC1-VCC)") (class "Default")
      (node (ref "C6") (pin "1") (pinfunction "1_1") (pintype "passive"))
      (node (ref "C8") (pin "1") (pinfunction "1_1") (pintype "passive"))
      (node (ref "IC1") (pin "24") (pinfunction "VCC_24") (pintype "bidirectional"))
      (node (ref "L2") (pin "1") (pinfunction "1_1") (pintype "passive"))
    )
    (net (code "60") (name "Net-(IC2-VI)") (class "Default")
      (node (ref "C19") (pin "1") (pinfunction "1_1") (pintype "passive"))
      (node (ref "IC2") (pin "1") (pinfunction "VI_1") (pintype "input"))
      (node (ref "L3") (pin "2") (pinfunction "2_2") (pintype "passive"))
    )
    (net (code "61") (name "Net-(IC3A-X1)") (class "Default")
      (node (ref "IC3") (pin "14") (pinfunction "X1_14") (pintype "bidirectional"))
      (node (ref "R87") (pin "P$2") (pinfunction "S_P$2") (pintype "passive"))
    )
    (net (code "62") (name "Net-(IC3A-X2)") (class "Default")
      (node (ref "IC3") (pin "15") (pinfunction "X2_15") (pintype "bidirectional"))
      (node (ref "R88") (pin "P$2") (pinfunction "S_P$2") (pintype "passive"))
    )
    (net (code "63") (name "Net-(IC3A-X4)") (class "Default")
      (node (ref "IC3") (pin "1") (pinfunction "X4_1") (pintype "bidirectional"))
      (node (ref "R86") (pin "P$2") (pinfunction "S_P$2") (pintype "passive"))
    )
    (net (code "64") (name "Net-(IC3A-X5)") (class "Default")
      (node (ref "IC3") (pin "5") (pinfunction "X5_5") (pintype "bidirectional"))
      (node (ref "R84") (pin "P$2") (pinfunction "S_P$2") (pintype "passive"))
    )
    (net (code "65") (name "Net-(IC3A-X6)") (class "Default")
      (node (ref "IC3") (pin "2") (pinfunction "X6_2") (pintype "bidirectional"))
      (node (ref "R85") (pin "P$2") (pinfunction "S_P$2") (pintype "passive"))
    )
    (net (code "66") (name "Net-(IC3A-X7)") (class "Default")
      (node (ref "IC3") (pin "4") (pinfunction "X7_4") (pintype "bidirectional"))
      (node (ref "R89") (pin "P$2") (pinfunction "S_P$2") (pintype "passive"))
    )
    (net (code "67") (name "Net-(IC5-PF0{slash}OSC_IN{slash}I2C2_SDA)") (class "Default")
      (node (ref "IC5") (pin "5") (pinfunction "PF0/OSC_IN/I2C2_SDA_5") (pintype "bidirectional"))
      (node (ref "R9") (pin "1") (pinfunction "1_1") (pintype "passive"))
    )
    (net (code "68") (name "Net-(IC5-PF1{slash}OSC_OUT{slash}I2C2_SCL)") (class "Default")
      (node (ref "IC5") (pin "6") (pinfunction "PF1/OSC_OUT/I2C2_SCL_6") (pintype "bidirectional"))
      (node (ref "R8") (pin "1") (pinfunction "1_1") (pintype "passive"))
    )
    (net (code "69") (name "Net-(IC6A-X0)") (class "Default")
      (node (ref "IC6") (pin "13") (pinfunction "X0_13") (pintype "bidirectional"))
      (node (ref "R81") (pin "2") (pinfunction "S_2") (pintype "passive"))
    )
    (net (code "70") (name "Net-(IC6A-X1)") (class "Default")
      (node (ref "IC6") (pin "14") (pinfunction "X1_14") (pintype "bidirectional"))
      (node (ref "R80") (pin "2") (pinfunction "S_2") (pintype "passive"))
    )
    (net (code "71") (name "Net-(IC6A-X2)") (class "Default")
      (node (ref "IC6") (pin "15") (pinfunction "X2_15") (pintype "bidirectional"))
      (node (ref "R79") (pin "2") (pinfunction "S_2") (pintype "passive"))
    )
    (net (code "72") (name "Net-(IC6A-X3)") (class "Default")
      (node (ref "IC6") (pin "12") (pinfunction "X3_12") (pintype "bidirectional"))
      (node (ref "R82") (pin "2") (pinfunction "S_2") (pintype "passive"))
    )
    (net (code "73") (name "Net-(IC6A-X4)") (class "Default")
      (node (ref "IC6") (pin "1") (pinfunction "X4_1") (pintype "bidirectional"))
      (node (ref "R78") (pin "2") (pinfunction "S_2") (pintype "passive"))
    )
    (net (code "74") (name "Net-(IC6A-X6)") (class "Default")
      (node (ref "IC6") (pin "2") (pinfunction "X6_2") (pintype "bidirectional"))
      (node (ref "R83") (pin "2") (pinfunction "S_2") (pintype "passive"))
    )
    (net (code "75") (name "Net-(IC7-VI)") (class "Default")
      (node (ref "C23") (pin "1") (pinfunction "1_1") (pintype "passive"))
      (node (ref "IC7") (pin "3") (pinfunction "VI_3") (pintype "input"))
      (node (ref "L4") (pin "1") (pinfunction "1_1") (pintype "passive"))
    )
    (net (code "76") (name "Net-(IC8A--IN)") (class "Default")
      (node (ref "C28") (pin "1") (pinfunction "1_1") (pintype "passive"))
      (node (ref "IC8") (pin "2") (pinfunction "-IN_2") (pintype "input"))
      (node (ref "R20") (pin "2") (pinfunction "2_2") (pintype "passive"))
      (node (ref "R23") (pin "1") (pinfunction "1_1") (pintype "passive"))
      (node (ref "R32") (pin "1") (pinfunction "1_1") (pintype "passive"))
    )
    (net (code "77") (name "Net-(IC8B--IN)") (class "Default")
      (node (ref "C27") (pin "1") (pinfunction "1_1") (pintype "passive"))
      (node (ref "IC8") (pin "6") (pinfunction "-IN_6") (pintype "input"))
      (node (ref "R19") (pin "2") (pinfunction "2_2") (pintype "passive"))
      (node (ref "R24") (pin "1") (pinfunction "1_1") (pintype "passive"))
      (node (ref "R31") (pin "1") (pinfunction "1_1") (pintype "passive"))
    )
    (net (code "78") (name "Net-(IC9A--IN)") (class "Default")
      (node (ref "C29") (pin "1") (pinfunction "1_1") (pintype "passive"))
      (node (ref "IC9") (pin "2") (pinfunction "-IN_2") (pintype "input"))
      (node (ref "R15") (pin "2") (pinfunction "2_2") (pintype "passive"))
      (node (ref "R22") (pin "1") (pinfunction "1_1") (pintype "passive"))
      (node (ref "R25") (pin "1") (pinfunction "1_1") (pintype "passive"))
    )
    (net (code "79") (name "Net-(IC9B--IN)") (class "Default")
      (node (ref "C31") (pin "1") (pinfunction "1_1") (pintype "passive"))
      (node (ref "IC9") (pin "6") (pinfunction "-IN_6") (pintype "input"))
      (node (ref "R13") (pin "2") (pinfunction "2_2") (pintype "passive"))
      (node (ref "R26") (pin "1") (pinfunction "1_1") (pintype "passive"))
      (node (ref "R27") (pin "1") (pinfunction "1_1") (pintype "passive"))
    )
    (net (code "80") (name "Net-(IC10A--IN)") (class "Default")
      (node (ref "C32") (pin "1") (pinfunction "1_1") (pintype "passive"))
      (node (ref "IC10") (pin "2") (pinfunction "-IN_2") (pintype "input"))
      (node (ref "R14") (pin "2") (pinfunction "2_2") (pintype "passive"))
      (node (ref "R21") (pin "1") (pinfunction "1_1") (pintype "passive"))
      (node (ref "R28") (pin "1") (pinfunction "1_1") (pintype "passive"))
    )
    (net (code "81") (name "Net-(IC10B--IN)") (class "Default")
      (node (ref "C35") (pin "1") (pinfunction "1_1") (pintype "passive"))
      (node (ref "IC10") (pin "6") (pinfunction "-IN_6") (pintype "input"))
      (node (ref "R16") (pin "2") (pinfunction "2_2") (pintype "passive"))
      (node (ref "R29") (pin "1") (pinfunction "1_1") (pintype "passive"))
      (node (ref "R30") (pin "1") (pinfunction "1_1") (pintype "passive"))
    )
    (net (code "82") (name "Net-(IC12A--IN)") (class "Default")
      (node (ref "C44") (pin "1") (pinfunction "1_1") (pintype "passive"))
      (node (ref "IC12") (pin "2") (pinfunction "-IN_2") (pintype "input"))
      (node (ref "R41") (pin "2") (pinfunction "2_2") (pintype "passive"))
      (node (ref "R47") (pin "1") (pinfunction "1_1") (pintype "passive"))
    )
    (net (code "83") (name "Net-(IC12A-OUT)") (class "Default")
      (node (ref "C44") (pin "2") (pinfunction "2_2") (pintype "passive"))
      (node (ref "IC12") (pin "1") (pinfunction "OUT_1") (pintype "output"))
      (node (ref "IC12") (pin "5") (pinfunction "+IN_5") (pintype "input"))
      (node (ref "R35") (pin "2") (pinfunction "2_2") (pintype "passive"))
    )
    (net (code "84") (name "Net-(IC12B--IN)") (class "Default")
      (node (ref "IC12") (pin "6") (pinfunction "-IN_6") (pintype "input"))
      (node (ref "LED4") (pin "2") (pinfunction "2_2") (pintype "bidirectional"))
      (node (ref "R54") (pin "1") (pinfunction "1_1") (pintype "passive"))
    )
    (net (code "85") (name "Net-(IC12B-OUT)") (class "Default")
      (node (ref "IC12") (pin "7") (pinfunction "OUT_7") (pintype "output"))
      (node (ref "LED4") (pin "1") (pinfunction "1_1") (pintype "bidirectional"))
    )
    (net (code "86") (name "Net-(IC12C-+IN)") (class "Default")
      (node (ref "C45") (pin "2") (pinfunction "2_2") (pintype "passive"))
      (node (ref "IC12") (pin "10") (pinfunction "+IN_10") (pintype "input"))
      (node (ref "IC12") (pin "14") (pinfunction "OUT_14") (pintype "output"))
      (node (ref "R34") (pin "2") (pinfunction "2_2") (pintype "passive"))
    )
    (net (code "87") (name "Net-(IC12C--IN)") (class "Default")
      (node (ref "IC12") (pin "9") (pinfunction "-IN_9") (pintype "input"))
      (node (ref "LED6") (pin "2") (pinfunction "2_2") (pintype "bidirectional"))
      (node (ref "R55") (pin "1") (pinfunction "1_1") (pintype "passive"))
    )
    (net (code "88") (name "Net-(IC12C-OUT)") (class "Default")
      (node (ref "IC12") (pin "8") (pinfunction "OUT_8") (pintype "output"))
      (node (ref "LED6") (pin "1") (pinfunction "1_1") (pintype "bidirectional"))
    )
    (net (code "89") (name "Net-(IC12D--IN)") (class "Default")
      (node (ref "C45") (pin "1") (pinfunction "1_1") (pintype "passive"))
      (node (ref "IC12") (pin "13") (pinfunction "-IN_13") (pintype "input"))
      (node (ref "R42") (pin "2") (pinfunction "2_2") (pintype "passive"))
      (node (ref "R50") (pin "1") (pinfunction "1_1") (pintype "passive"))
    )
    (net (code "90") (name "Net-(IC13A--IN)") (class "Default")
      (node (ref "C46") (pin "1") (pinfunction "1_1") (pintype "passive"))
      (node (ref "IC13") (pin "2") (pinfunction "-IN_2") (pintype "input"))
      (node (ref "R43") (pin "2") (pinfunction "2_2") (pintype "passive"))
      (node (ref "R49") (pin "1") (pinfunction "1_1") (pintype "passive"))
    )
    (net (code "91") (name "Net-(IC13A-OUT)") (class "Default")
      (node (ref "C46") (pin "2") (pinfunction "2_2") (pintype "passive"))
      (node (ref "IC13") (pin "1") (pinfunction "OUT_1") (pintype "output"))
      (node (ref "IC13") (pin "5") (pinfunction "+IN_5") (pintype "input"))
      (node (ref "R36") (pin "2") (pinfunction "2_2") (pintype "passive"))
    )
    (net (code "92") (name "Net-(IC13B--IN)") (class "Default")
      (node (ref "IC13") (pin "6") (pinfunction "-IN_6") (pintype "input"))
      (node (ref "LED3") (pin "2") (pinfunction "2_2") (pintype "bidirectional"))
      (node (ref "R56") (pin "1") (pinfunction "1_1") (pintype "passive"))
    )
    (net (code "93") (name "Net-(IC13B-OUT)") (class "Default")
      (node (ref "IC13") (pin "7") (pinfunction "OUT_7") (pintype "output"))
      (node (ref "LED3") (pin "1") (pinfunction "1_1") (pintype "bidirectional"))
    )
    (net (code "94") (name "Net-(IC13C-+IN)") (class "Default")
      (node (ref "C47") (pin "2") (pinfunction "2_2") (pintype "passive"))
      (node (ref "IC13") (pin "10") (pinfunction "+IN_10") (pintype "input"))
      (node (ref "IC13") (pin "14") (pinfunction "OUT_14") (pintype "output"))
      (node (ref "R38") (pin "2") (pinfunction "2_2") (pintype "passive"))
    )
    (net (code "95") (name "Net-(IC13C--IN)") (class "Default")
      (node (ref "IC13") (pin "9") (pinfunction "-IN_9") (pintype "input"))
      (node (ref "LED2") (pin "2") (pinfunction "2_2") (pintype "bidirectional"))
      (node (ref "R57") (pin "1") (pinfunction "1_1") (pintype "passive"))
    )
    (net (code "96") (name "Net-(IC13C-OUT)") (class "Default")
      (node (ref "IC13") (pin "8") (pinfunction "OUT_8") (pintype "output"))
      (node (ref "LED2") (pin "1") (pinfunction "1_1") (pintype "bidirectional"))
    )
    (net (code "97") (name "Net-(IC13D--IN)") (class "Default")
      (node (ref "C47") (pin "1") (pinfunction "1_1") (pintype "passive"))
      (node (ref "IC13") (pin "13") (pinfunction "-IN_13") (pintype "input"))
      (node (ref "R44") (pin "2") (pinfunction "2_2") (pintype "passive"))
      (node (ref "R53") (pin "1") (pinfunction "1_1") (pintype "passive"))
    )
    (net (code "98") (name "Net-(IC14A--IN)") (class "Default")
      (node (ref "C48") (pin "1") (pinfunction "1_1") (pintype "passive"))
      (node (ref "IC14") (pin "2") (pinfunction "-IN_2") (pintype "input"))
      (node (ref "R45") (pin "2") (pinfunction "2_2") (pintype "passive"))
      (node (ref "R51") (pin "1") (pinfunction "1_1") (pintype "passive"))
    )
    (net (code "99") (name "Net-(IC14A-OUT)") (class "Default")
      (node (ref "C48") (pin "2") (pinfunction "2_2") (pintype "passive"))
      (node (ref "IC14") (pin "1") (pinfunction "OUT_1") (pintype "output"))
      (node (ref "IC14") (pin "5") (pinfunction "+IN_5") (pintype "input"))
      (node (ref "R37") (pin "2") (pinfunction "2_2") (pintype "passive"))
    )
    (net (code "100") (name "Net-(IC14B--IN)") (class "Default")
      (node (ref "IC14") (pin "6") (pinfunction "-IN_6") (pintype "input"))
      (node (ref "LED5") (pin "2") (pinfunction "2_2") (pintype "bidirectional"))
      (node (ref "R58") (pin "1") (pinfunction "1_1") (pintype "passive"))
    )
    (net (code "101") (name "Net-(IC14B-OUT)") (class "Default")
      (node (ref "IC14") (pin "7") (pinfunction "OUT_7") (pintype "output"))
      (node (ref "LED5") (pin "1") (pinfunction "1_1") (pintype "bidirectional"))
    )
    (net (code "102") (name "Net-(IC14C-+IN)") (class "Default")
      (node (ref "C49") (pin "2") (pinfunction "2_2") (pintype "passive"))
      (node (ref "IC14") (pin "10") (pinfunction "+IN_10") (pintype "input"))
      (node (ref "IC14") (pin "14") (pinfunction "OUT_14") (pintype "output"))
      (node (ref "R39") (pin "2") (pinfunction "2_2") (pintype "passive"))
    )
    (net (code "103") (name "Net-(IC14C--IN)") (class "Default")
      (node (ref "IC14") (pin "9") (pinfunction "-IN_9") (pintype "input"))
      (node (ref "LED1") (pin "2") (pinfunction "2_2") (pintype "bidirectional"))
      (node (ref "R59") (pin "1") (pinfunction "1_1") (pintype "passive"))
    )
    (net (code "104") (name "Net-(IC14C-OUT)") (class "Default")
      (node (ref "IC14") (pin "8") (pinfunction "OUT_8") (pintype "output"))
      (node (ref "LED1") (pin "1") (pinfunction "1_1") (pintype "bidirectional"))
    )
    (net (code "105") (name "Net-(IC14D--IN)") (class "Default")
      (node (ref "C49") (pin "1") (pinfunction "1_1") (pintype "passive"))
      (node (ref "IC14") (pin "13") (pinfunction "-IN_13") (pintype "input"))
      (node (ref "R46") (pin "2") (pinfunction "2_2") (pintype "passive"))
      (node (ref "R52") (pin "1") (pinfunction "1_1") (pintype "passive"))
    )
    (net (code "106") (name "Net-(J1-3)") (class "Default")
      (node (ref "J1") (pin "P3") (pinfunction "3_P3") (pintype "passive"))
      (node (ref "R39") (pin "1") (pinfunction "1_1") (pintype "passive"))
      (node (ref "R46") (pin "1") (pinfunction "1_1") (pintype "passive"))
    )
    (net (code "107") (name "Net-(J2-3)") (class "Default")
      (node (ref "J2") (pin "P3") (pinfunction "3_P3") (pintype "passive"))
      (node (ref "R37") (pin "1") (pinfunction "1_1") (pintype "passive"))
      (node (ref "R45") (pin "1") (pinfunction "1_1") (pintype "passive"))
    )
    (net (code "108") (name "Net-(J3-3)") (class "Default")
      (node (ref "J3") (pin "P3") (pinfunction "3_P3") (pintype "passive"))
      (node (ref "R38") (pin "1") (pinfunction "1_1") (pintype "passive"))
      (node (ref "R44") (pin "1") (pinfunction "1_1") (pintype "passive"))
    )
    (net (code "109") (name "Net-(J4-3)") (class "Default")
      (node (ref "J4") (pin "P3") (pinfunction "3_P3") (pintype "passive"))
      (node (ref "R36") (pin "1") (pinfunction "1_1") (pintype "passive"))
      (node (ref "R43") (pin "1") (pinfunction "1_1") (pintype "passive"))
    )
    (net (code "110") (name "Net-(J5-3)") (class "Default")
      (node (ref "J5") (pin "P3") (pinfunction "3_P3") (pintype "passive"))
      (node (ref "R34") (pin "1") (pinfunction "1_1") (pintype "passive"))
      (node (ref "R42") (pin "1") (pinfunction "1_1") (pintype "passive"))
    )
    (net (code "111") (name "Net-(J6-3)") (class "Default")
      (node (ref "J6") (pin "P3") (pinfunction "3_P3") (pintype "passive"))
      (node (ref "R35") (pin "1") (pinfunction "1_1") (pintype "passive"))
      (node (ref "R41") (pin "1") (pinfunction "1_1") (pintype "passive"))
    )
    (net (code "112") (name "Net-(J7-2)") (class "Default")
      (node (ref "J7") (pin "P2") (pinfunction "2_P2") (pintype "passive"))
      (node (ref "R65") (pin "2") (pinfunction "2_2") (pintype "passive"))
    )
    (net (code "113") (name "Net-(J7-3)") (class "Default")
      (node (ref "J7") (pin "P3") (pinfunction "3_P3") (pintype "passive"))
      (node (ref "R66") (pin "1") (pinfunction "1_1") (pintype "passive"))
    )
    (net (code "114") (name "Net-(J8-2)") (class "Default")
      (node (ref "J8") (pin "P2") (pinfunction "2_P2") (pintype "passive"))
      (node (ref "R62") (pin "2") (pinfunction "2_2") (pintype "passive"))
    )
    (net (code "115") (name "Net-(J8-3)") (class "Default")
      (node (ref "J8") (pin "P3") (pinfunction "3_P3") (pintype "passive"))
      (node (ref "R77") (pin "1") (pinfunction "1_1") (pintype "passive"))
    )
    (net (code "116") (name "Net-(J9-2)") (class "Default")
      (node (ref "J9") (pin "P2") (pinfunction "2_P2") (pintype "passive"))
      (node (ref "R63") (pin "2") (pinfunction "2_2") (pintype "passive"))
    )
    (net (code "117") (name "Net-(J9-3)") (class "Default")
      (node (ref "J9") (pin "P3") (pinfunction "3_P3") (pintype "passive"))
      (node (ref "R68") (pin "1") (pinfunction "1_1") (pintype "passive"))
    )
    (net (code "118") (name "Net-(J10-2)") (class "Default")
      (node (ref "J10") (pin "P2") (pinfunction "2_P2") (pintype "passive"))
      (node (ref "R61") (pin "2") (pinfunction "2_2") (pintype "passive"))
    )
    (net (code "119") (name "Net-(J10-3)") (class "Default")
      (node (ref "J10") (pin "P3") (pinfunction "3_P3") (pintype "passive"))
      (node (ref "R76") (pin "1") (pinfunction "1_1") (pintype "passive"))
    )
    (net (code "120") (name "Net-(J11-2)") (class "Default")
      (node (ref "J11") (pin "P2") (pinfunction "2_P2") (pintype "passive"))
      (node (ref "R64") (pin "2") (pinfunction "2_2") (pintype "passive"))
    )
    (net (code "121") (name "Net-(J11-3)") (class "Default")
      (node (ref "J11") (pin "P3") (pinfunction "3_P3") (pintype "passive"))
      (node (ref "R67") (pin "1") (pinfunction "1_1") (pintype "passive"))
    )
    (net (code "122") (name "Net-(J12-2)") (class "Default")
      (node (ref "J12") (pin "P2") (pinfunction "2_P2") (pintype "passive"))
      (node (ref "R60") (pin "2") (pinfunction "2_2") (pintype "passive"))
    )
    (net (code "123") (name "Net-(J12-3)") (class "Default")
      (node (ref "J12") (pin "P3") (pinfunction "3_P3") (pintype "passive"))
      (node (ref "R75") (pin "1") (pinfunction "1_1") (pintype "passive"))
    )
    (net (code "124") (name "Net-(J13-3)") (class "Default")
      (node (ref "C38") (pin "1") (pinfunction "1_1") (pintype "passive"))
      (node (ref "J13") (pin "P3") (pinfunction "3_P3") (pintype "passive"))
      (node (ref "R30") (pin "2") (pinfunction "2_2") (pintype "passive"))
    )
    (net (code "125") (name "Net-(J14-3)") (class "Default")
      (node (ref "C39") (pin "1") (pinfunction "1_1") (pintype "passive"))
      (node (ref "J14") (pin "P3") (pinfunction "3_P3") (pintype "passive"))
      (node (ref "R28") (pin "2") (pinfunction "2_2") (pintype "passive"))
    )
    (net (code "126") (name "Net-(J15-3)") (class "Default")
      (node (ref "C37") (pin "1") (pinfunction "1_1") (pintype "passive"))
      (node (ref "J15") (pin "P3") (pinfunction "3_P3") (pintype "passive"))
      (node (ref "R27") (pin "2") (pinfunction "2_2") (pintype "passive"))
    )
    (net (code "127") (name "Net-(J16-3)") (class "Default")
      (node (ref "C40") (pin "1") (pinfunction "1_1") (pintype "passive"))
      (node (ref "J16") (pin "P3") (pinfunction "3_P3") (pintype "passive"))
      (node (ref "R25") (pin "2") (pinfunction "2_2") (pintype "passive"))
    )
    (net (code "128") (name "Net-(J17-3)") (class "Default")
      (node (ref "C36") (pin "1") (pinfunction "1_1") (pintype "passive"))
      (node (ref "J17") (pin "P3") (pinfunction "3_P3") (pintype "passive"))
      (node (ref "R31") (pin "2") (pinfunction "2_2") (pintype "passive"))
    )
    (net (code "129") (name "Net-(J18-3)") (class "Default")
      (node (ref "C42") (pin "1") (pinfunction "1_1") (pintype "passive"))
      (node (ref "J18") (pin "P3") (pinfunction "3_P3") (pintype "passive"))
      (node (ref "R32") (pin "2") (pinfunction "2_2") (pintype "passive"))
    )
    (net (code "130") (name "Net-(JP3-Pad2)") (class "Default")
      (node (ref "JP3") (pin "2") (pinfunction "2_2") (pintype "passive"))
      (node (ref "R5") (pin "2") (pinfunction "2_2") (pintype "passive"))
    )
    (net (code "131") (name "Net-(JP3-Pad3)") (class "Default")
      (node (ref "JP3") (pin "3") (pinfunction "3_3") (pintype "passive"))
      (node (ref "R7") (pin "2") (pinfunction "2_2") (pintype "passive"))
    )
    (net (code "132") (name "Net-(JP4-Pad2)") (class "Default")
      (node (ref "JP4") (pin "2") (pinfunction "2_2") (pintype "passive"))
      (node (ref "R10") (pin "2") (pinfunction "2_2") (pintype "passive"))
    )
    (net (code "133") (name "Net-(JP4-Pad3)") (class "Default")
      (node (ref "JP4") (pin "3") (pinfunction "3_3") (pintype "passive"))
      (node (ref "R11") (pin "2") (pinfunction "2_2") (pintype "passive"))
    )
    (net (code "134") (name "Net-(Q1B-2)") (class "Default")
      (node (ref "C4") (pin "2") (pinfunction "2_2") (pintype "passive"))
      (node (ref "Q1") (pin "3") (pinfunction "2_3") (pintype "passive"))
      (node (ref "R8") (pin "2") (pinfunction "2_2") (pintype "passive"))
    )
    (net (code "135") (name "Net-(R78A-A)") (class "Default")
      (node (ref "R17") (pin "1") (pinfunction "1_1") (pintype "passive"))
      (node (ref "R78") (pin "B") (pinfunction "A_B") (pintype "passive"))
    )
    (net (code "136") (name "Net-(R79A-A)") (class "Default")
      (node (ref "R3") (pin "1") (pinfunction "1_1") (pintype "passive"))
      (node (ref "R79") (pin "B") (pinfunction "A_B") (pintype "passive"))
    )
    (net (code "137") (name "Net-(R80A-A)") (class "Default")
      (node (ref "R1") (pin "1") (pinfunction "1_1") (pintype "passive"))
      (node (ref "R80") (pin "B") (pinfunction "A_B") (pintype "passive"))
    )
    (net (code "138") (name "Net-(R81A-A)") (class "Default")
      (node (ref "R2") (pin "1") (pinfunction "1_1") (pintype "passive"))
      (node (ref "R81") (pin "B") (pinfunction "A_B") (pintype "passive"))
    )
    (net (code "139") (name "Net-(R82A-A)") (class "Default")
      (node (ref "R4") (pin "1") (pinfunction "1_1") (pintype "passive"))
      (node (ref "R82") (pin "B") (pinfunction "A_B") (pintype "passive"))
    )
    (net (code "140") (name "Net-(R83A-A)") (class "Default")
      (node (ref "R18") (pin "1") (pinfunction "1_1") (pintype "passive"))
      (node (ref "R83") (pin "B") (pinfunction "A_B") (pintype "passive"))
    )
    (net (code "141") (name "POTS_ADDR_A") (class "Default")
      (node (ref "IC3") (pin "9") (pinfunction "C_9") (pintype "input"))
      (node (ref "IC5") (pin "21") (pinfunction "PA5/SPI1_SCK/I2S1_CK/TIM2_CH1/ADC_IN5/DAC1_OUT2_21") (pintype "bidirectional"))
      (node (ref "IC6") (pin "11") (pinfunction "A_11") (pintype "input"))
    )
    (net (code "142") (name "POTS_ADDR_B") (class "Default")
      (node (ref "IC3") (pin "10") (pinfunction "B_10") (pintype "input"))
      (node (ref "IC5") (pin "20") (pinfunction "PA4/SPI1_NSS/I2S1_WS/SPI3_NSS/I2S3_WS/USART2_CK/TIM3_CH2/ADC_IN4/DAC1_OUT1_20") (pintype "bidirectional"))
      (node (ref "IC6") (pin "10") (pinfunction "B_10") (pintype "input"))
    )
    (net (code "143") (name "POTS_ADDR_C") (class "Default")
      (node (ref "IC3") (pin "11") (pinfunction "A_11") (pintype "input"))
      (node (ref "IC5") (pin "18") (pinfunction "PA3/SPI3_MOSI/I2S3_SD/USART2_RX/TIM2_CH4/TIM5_CH4/ADC_IN3_18") (pintype "bidirectional"))
      (node (ref "IC6") (pin "9") (pinfunction "C_9") (pintype "input"))
    )
    (net (code "144") (name "RESET") (class "Default")
      (node (ref "IC5") (pin "7") (pinfunction "NRST_7") (pintype "bidirectional"))
      (node (ref "JP6") (pin "4") (pinfunction "4_4") (pintype "passive"))
      (node (ref "R12") (pin "1") (pinfunction "1_1") (pintype "passive"))
    )
    (net (code "145") (name "RIGHT_RX") (class "Default")
      (node (ref "IC5") (pin "25") (pinfunction "PC5/USART1_RX/ADC_IN15_25") (pintype "bidirectional"))
      (node (ref "R10") (pin "1") (pinfunction "1_1") (pintype "passive"))
    )
    (net (code "146") (name "RIGHT_TX") (class "Default")
      (node (ref "IC5") (pin "24") (pinfunction "PC4/USART1_TX/ADC_IN14_24") (pintype "bidirectional"))
      (node (ref "R11") (pin "1") (pinfunction "1_1") (pintype "passive"))
    )
    (net (code "147") (name "STAGE_LED_1") (class "Default")
      (node (ref "IC5") (pin "45") (pinfunction "PA12/SPI1_SCK/I2S1_CK/USART1_RTS/CAN_TX/TIM4_CH2/TIM5_CH3_45") (pintype "bidirectional"))
      (node (ref "R17") (pin "2") (pinfunction "2_2") (pintype "passive"))
    )
    (net (code "148") (name "STAGE_LED_2") (class "Default")
      (node (ref "IC5") (pin "2") (pinfunction "PC13/TIMESTAMP/RTC_TAMPER1_2") (pintype "bidirectional"))
      (node (ref "R3") (pin "2") (pinfunction "2_2") (pintype "passive"))
    )
    (net (code "149") (name "STAGE_LED_3") (class "Default")
      (node (ref "IC5") (pin "3") (pinfunction "PC14/OSC32_IN_3") (pintype "bidirectional"))
      (node (ref "R1") (pin "2") (pinfunction "2_2") (pintype "passive"))
    )
    (net (code "150") (name "STAGE_LED_4") (class "Default")
      (node (ref "IC5") (pin "4") (pinfunction "PC15/OSC32_OUT_4") (pintype "bidirectional"))
      (node (ref "R2") (pin "2") (pinfunction "2_2") (pintype "passive"))
    )
    (net (code "151") (name "STAGE_LED_5") (class "Default")
      (node (ref "IC5") (pin "16") (pinfunction "PA2/SPI3_MISO/I2S3_MCK/USART2_TX/TIM2_CH3/TIM5_CH3/ADC_IN2_16") (pintype "bidirectional"))
      (node (ref "R4") (pin "2") (pinfunction "2_2") (pintype "passive"))
    )
    (net (code "152") (name "STAGE_LED_6") (class "Default")
      (node (ref "IC5") (pin "28") (pinfunction "PB2/SDADC_AIN4P/SDADC2_AIN6P_28") (pintype "bidirectional"))
      (node (ref "R18") (pin "2") (pinfunction "2_2") (pintype "passive"))
    )
    (net (code "153") (name "SWCLK") (class "Default")
      (node (ref "IC5") (pin "49") (pinfunction "PA14/I2C1_SDA/JTCK-SWCLK_49") (pintype "bidirectional"))
      (node (ref "JP6") (pin "3") (pinfunction "3_3") (pintype "passive"))
    )
    (net (code "154") (name "SWDIO") (class "Default")
      (node (ref "IC5") (pin "46") (pinfunction "PA13/SPI1_MISO/I2S1_MCK/USART3_CTS/TIM4_CH3/TIM5_CH4/JTMS-SWDIO_46") (pintype "bidirectional"))
      (node (ref "JP6") (pin "2") (pinfunction "2_2") (pintype "passive"))
    )
    (net (code "155") (name "SW_MODE_1") (class "Default")
      (node (ref "IC5") (pin "8") (pinfunction "PC0/TIM5_CH1/ADC_IN10_8") (pintype "bidirectional"))
      (node (ref "SW1") (pin "3") (pinfunction "3_3") (pintype "passive"))
      (node (ref "SW1") (pin "4") (pinfunction "4_4") (pintype "passive"))
    )
    (net (code "156") (name "SW_MODE_2") (class "Default")
      (node (ref "IC5") (pin "9") (pinfunction "PC1/TIM5_CH2/ADC_IN11_9") (pintype "bidirectional"))
      (node (ref "SW2") (pin "3") (pinfunction "3_3") (pintype "passive"))
      (node (ref "SW2") (pin "4") (pinfunction "4_4") (pintype "passive"))
    )
    (net (code "157") (name "SW_MODE_3") (class "Default")
      (node (ref "IC5") (pin "10") (pinfunction "PC2/SPI2_MISO/I2S2_MCK/TIM5_CH3/ADC_IN12_10") (pintype "bidirectional"))
      (node (ref "SW3") (pin "3") (pinfunction "3_3") (pintype "passive"))
      (node (ref "SW3") (pin "4") (pinfunction "4_4") (pintype "passive"))
    )
    (net (code "158") (name "SW_MODE_4") (class "Default")
      (node (ref "IC5") (pin "11") (pinfunction "PC3/SPI2_MOSI/I2S2_SD/TIM5_CH4/ADC_IN13_11") (pintype "bidirectional"))
      (node (ref "SW4") (pin "3") (pinfunction "3_3") (pintype "passive"))
      (node (ref "SW4") (pin "4") (pinfunction "4_4") (pintype "passive"))
    )
    (net (code "159") (name "SW_MODE_5") (class "Default")
      (node (ref "IC5") (pin "14") (pinfunction "PA0/USART2_CTS/TIM2_CH1/TIM5_CH1/ADC_IN0_14") (pintype "bidirectional"))
      (node (ref "SW5") (pin "3") (pinfunction "3_3") (pintype "passive"))
      (node (ref "SW5") (pin "4") (pinfunction "4_4") (pintype "passive"))
    )
    (net (code "160") (name "SW_MODE_6") (class "Default")
      (node (ref "IC5") (pin "15") (pinfunction "PA1/SPI3_SCK/I2S3_CK/USART2_RTS/TIM2_CH2/TIM5_CH2/ADC_IN1_15") (pintype "bidirectional"))
      (node (ref "SW6") (pin "3") (pinfunction "3_3") (pintype "passive"))
      (node (ref "SW6") (pin "4") (pinfunction "4_4") (pintype "passive"))
    )
    (net (code "161") (name "VCC") (class "Default")
      (node (ref "C21") (pin "1") (pinfunction "1_1") (pintype "passive"))
      (node (ref "C25") (pin "1") (pinfunction "1_1") (pintype "passive"))
      (node (ref "C50") (pin "1") (pinfunction "1_1") (pintype "passive"))
      (node (ref "C52") (pin "1") (pinfunction "1_1") (pintype "passive"))
      (node (ref "C54") (pin "1") (pinfunction "1_1") (pintype "passive"))
      (node (ref "IC12") (pin "4") (pinfunction "V+_4") (pintype "power_in"))
      (node (ref "IC13") (pin "4") (pinfunction "V+_4") (pintype "power_in"))
      (node (ref "IC14") (pin "4") (pinfunction "V+_4") (pintype "power_in"))
      (node (ref "L5") (pin "1") (pinfunction "1_1") (pintype "passive"))
    )
    (net (code "162") (name "VEE") (class "Default")
      (node (ref "C1") (pin "2") (pinfunction "2_2") (pintype "passive"))
      (node (ref "C2") (pin "2") (pinfunction "2_2") (pintype "passive"))
      (node (ref "C51") (pin "2") (pinfunction "2_2") (pintype "passive"))
      (node (ref "C53") (pin "2") (pinfunction "2_2") (pintype "passive"))
      (node (ref "C55") (pin "2") (pinfunction "2_2") (pintype "passive"))
      (node (ref "IC12") (pin "11") (pinfunction "V-_11") (pintype "power_in"))
      (node (ref "IC13") (pin "11") (pinfunction "V-_11") (pintype "power_in"))
      (node (ref "IC14") (pin "11") (pinfunction "V-_11") (pintype "power_in"))
      (node (ref "L1") (pin "1") (pinfunction "1_1") (pintype "passive"))
      (node (ref "R33") (pin "1") (pinfunction "1_1") (pintype "passive"))
    )
    (net (code "163") (name "VREF_BIAS") (class "Default")
      (node (ref "C43") (pin "1") (pinfunction "1_1") (pintype "passive"))
      (node (ref "IC12") (pin "12") (pinfunction "+IN_12") (pintype "input"))
      (node (ref "IC12") (pin "3") (pinfunction "+IN_3") (pintype "input"))
      (node (ref "IC13") (pin "12") (pinfunction "+IN_12") (pintype "input"))
      (node (ref "IC13") (pin "3") (pinfunction "+IN_3") (pintype "input"))
      (node (ref "IC14") (pin "12") (pinfunction "+IN_12") (pintype "input"))
      (node (ref "IC14") (pin "3") (pinfunction "+IN_3") (pintype "input"))
      (node (ref "R40") (pin "1") (pinfunction "1_1") (pintype "passive"))
      (node (ref "R48") (pin "2") (pinfunction "2_2") (pintype "passive"))
    )
    (net (code "164") (name "unconnected-(IC1-OUT0-Pad5)") (class "Default")
      (node (ref "IC1") (pin "5") (pinfunction "OUT0_5") (pintype "bidirectional"))
    )
    (net (code "165") (name "unconnected-(IC1-OUT1-Pad6)") (class "Default")
      (node (ref "IC1") (pin "6") (pinfunction "OUT1_6") (pintype "bidirectional"))
    )
    (net (code "166") (name "unconnected-(IC1-OUT14-Pad19)") (class "Default")
      (node (ref "IC1") (pin "19") (pinfunction "OUT14_19") (pintype "bidirectional"))
    )
    (net (code "167") (name "unconnected-(IC1-OUT15-Pad20)") (class "Default")
      (node (ref "IC1") (pin "20") (pinfunction "OUT15_20") (pintype "bidirectional"))
    )
    (net (code "168") (name "unconnected-(IC1-SOUT-Pad22)") (class "Default")
      (node (ref "IC1") (pin "22") (pinfunction "SOUT_22") (pintype "bidirectional"))
    )
    (net (code "169") (name "unconnected-(IC2-EN-Pad4)") (class "Default")
      (node (ref "IC2") (pin "4") (pinfunction "EN_4") (pintype "input"))
    )
    (net (code "170") (name "unconnected-(IC3A-X0-Pad13)") (class "Default")
      (node (ref "IC3") (pin "13") (pinfunction "X0_13") (pintype "bidirectional"))
    )
    (net (code "171") (name "unconnected-(IC3A-X3-Pad12)") (class "Default")
      (node (ref "IC3") (pin "12") (pinfunction "X3_12") (pintype "bidirectional"))
    )
    (net (code "172") (name "unconnected-(IC4-VOUTF-Pad9)") (class "Default")
      (node (ref "IC4") (pin "9") (pinfunction "VOUTF_9") (pintype "output"))
    )
    (net (code "173") (name "unconnected-(IC4-VOUTH-Pad8)") (class "Default")
      (node (ref "IC4") (pin "8") (pinfunction "VOUTH_8") (pintype "output"))
    )
    (net (code "174") (name "unconnected-(IC5-PB3{slash}SPI1_SCK{slash}I2S1_CK{slash}SPI3_SCK{slash}I2S3_CK{slash}USART2_TX{slash}TIM2_CH2{slash}JTDO{slash}SPI3_SCK{slash}JTDO-Pad55)") (class "Default")
      (node (ref "IC5") (pin "55") (pinfunction "PB3/SPI1_SCK/I2S1_CK/SPI3_SCK/I2S3_CK/USART2_TX/TIM2_CH2/JTDO/SPI3_SCK/JTDO_55") (pintype "bidirectional"))
    )
    (net (code "175") (name "unconnected-(IC5-PB4{slash}SPI1_MISO{slash}I2S1_MCK{slash}SPI3_MISO{slash}I2S3_MCK{slash}USART2_RX{slash}TIM3_CH1{slash}NJTRST-Pad56)") (class "Default")
      (node (ref "IC5") (pin "56") (pinfunction "PB4/SPI1_MISO/I2S1_MCK/SPI3_MISO/I2S3_MCK/USART2_RX/TIM3_CH1/NJTRST_56") (pintype "bidirectional"))
    )
    (net (code "176") (name "unconnected-(IC5-PC6{slash}SPI1_NSS{slash}I2S1_WS{slash}TIM3_CH1-Pad37)") (class "Default")
      (node (ref "IC5") (pin "37") (pinfunction "PC6/SPI1_NSS/I2S1_WS/TIM3_CH1_37") (pintype "bidirectional"))
    )
    (net (code "177") (name "unconnected-(IC5-PC11{slash}SPI3_MISO{slash}I2S3_MCK{slash}USART3_RX-Pad52)") (class "Default")
      (node (ref "IC5") (pin "52") (pinfunction "PC11/SPI3_MISO/I2S3_MCK/USART3_RX_52") (pintype "bidirectional"))
    )
    (net (code "178") (name "unconnected-(IC5-PD2{slash}TIM3_ETR-Pad54)") (class "Default")
      (node (ref "IC5") (pin "54") (pinfunction "PD2/TIM3_ETR_54") (pintype "bidirectional"))
    )
    (net (code "179") (name "unconnected-(IC5-PD8{slash}SPI2_SCK{slash}I2S2_CK{slash}USART3_TX{slash}SDADC3_AIN6P-Pad36)") (class "Default")
      (node (ref "IC5") (pin "36") (pinfunction "PD8/SPI2_SCK/I2S2_CK/USART3_TX/SDADC3_AIN6P_36") (pintype "bidirectional"))
    )
    (net (code "180") (name "unconnected-(IC5-PF6{slash}SPI1_MOSI{slash}I2S1_SD{slash}USART3_RTS{slash}TIM4_CH4{slash}I2C2_SCL-Pad47)") (class "Default")
      (node (ref "IC5") (pin "47") (pinfunction "PF6/SPI1_MOSI/I2S1_SD/USART3_RTS/TIM4_CH4/I2C2_SCL_47") (pintype "bidirectional"))
    )
    (net (code "181") (name "unconnected-(IC5-PF7{slash}I2C2_SDA{slash}USART2_CK-Pad48)") (class "Default")
      (node (ref "IC5") (pin "48") (pinfunction "PF7/I2C2_SDA/USART2_CK_48") (pintype "bidirectional"))
    )
    (net (code "182") (name "unconnected-(IC6A-X5-Pad5)") (class "Default")
      (node (ref "IC6") (pin "5") (pinfunction "X5_5") (pintype "bidirectional"))
    )
    (net (code "183") (name "unconnected-(IC6A-X7-Pad4)") (class "Default")
      (node (ref "IC6") (pin "4") (pinfunction "X7_4") (pintype "bidirectional"))
    )
    (net (code "184") (name "unconnected-(J1-2-PadP2)") (class "Default")
      (node (ref "J1") (pin "P2") (pinfunction "2_P2") (pintype "passive"))
    )
    (net (code "185") (name "unconnected-(J2-2-PadP2)") (class "Default")
      (node (ref "J2") (pin "P2") (pinfunction "2_P2") (pintype "passive"))
    )
    (net (code "186") (name "unconnected-(J3-2-PadP2)") (class "Default")
      (node (ref "J3") (pin "P2") (pinfunction "2_P2") (pintype "passive"))
    )
    (net (code "187") (name "unconnected-(J4-2-PadP2)") (class "Default")
      (node (ref "J4") (pin "P2") (pinfunction "2_P2") (pintype "passive"))
    )
    (net (code "188") (name "unconnected-(J5-2-PadP2)") (class "Default")
      (node (ref "J5") (pin "P2") (pinfunction "2_P2") (pintype "passive"))
    )
    (net (code "189") (name "unconnected-(J6-2-PadP2)") (class "Default")
      (node (ref "J6") (pin "P2") (pinfunction "2_P2") (pintype "passive"))
    )
  )
)
